# keyBoard_A.net
KiCad netlist of a schematic drawn in EAGLE
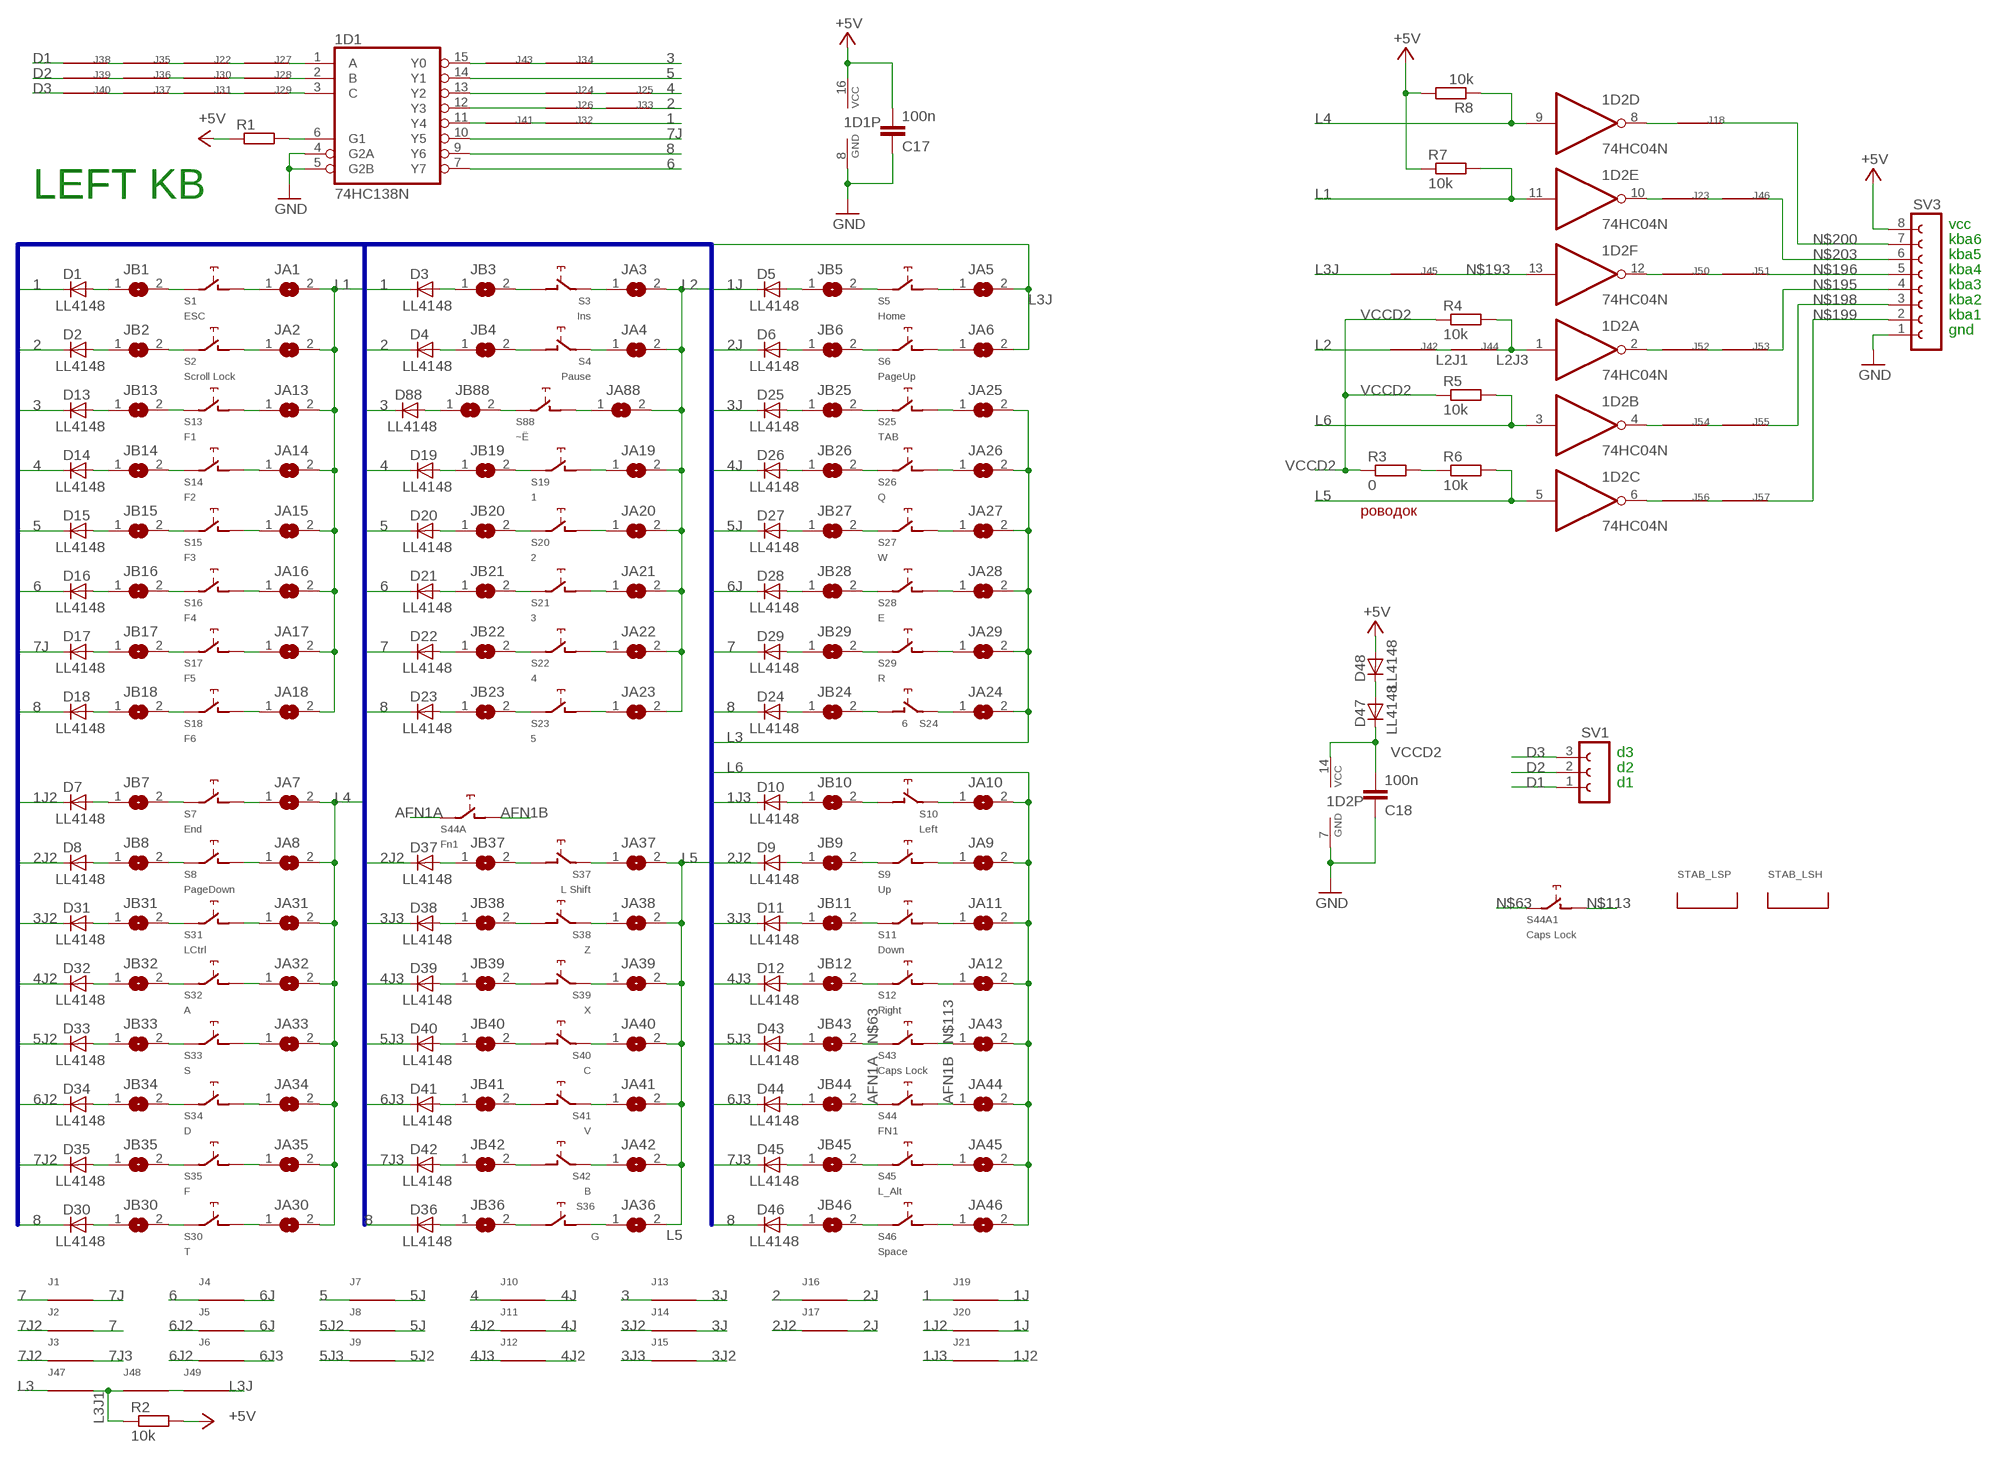
[diagram p0: schematic, sheet 1]

(export (version "E")
  (design (tool "Eeschema 10.0.6"))
  (components
    (comp (ref "1D1")
      (value "74HC138N")
      (footprint "eagle-import:DIL16")
      (libsource (lib "eagle-import") (part "74138NHC"))
    )
    (comp (ref "1D2")
      (value "74HC04N")
      (footprint "eagle-import:DIL14")
      (libsource (lib "eagle-import") (part "7404NACT"))
    )
    (comp (ref "C17")
      (value "100n")
      (footprint "eagle-import:C0805")
      (libsource (lib "eagle-import") (part "C-EUC0805"))
    )
    (comp (ref "C18")
      (value "100n")
      (footprint "eagle-import:C0805")
      (libsource (lib "eagle-import") (part "C-EUC0805"))
    )
    (comp (ref "D1")
      (value "LL4148")
      (footprint "eagle-import:SOD80C")
      (libsource (lib "eagle-import") (part "LL4148"))
    )
    (comp (ref "D2")
      (value "LL4148")
      (footprint "eagle-import:SOD80C")
      (libsource (lib "eagle-import") (part "LL4148"))
    )
    (comp (ref "D3")
      (value "LL4148")
      (footprint "eagle-import:SOD80C")
      (libsource (lib "eagle-import") (part "LL4148"))
    )
    (comp (ref "D4")
      (value "LL4148")
      (footprint "eagle-import:SOD80C")
      (libsource (lib "eagle-import") (part "LL4148"))
    )
    (comp (ref "D5")
      (value "LL4148")
      (footprint "eagle-import:SOD80C")
      (libsource (lib "eagle-import") (part "LL4148"))
    )
    (comp (ref "D6")
      (value "LL4148")
      (footprint "eagle-import:SOD80C")
      (libsource (lib "eagle-import") (part "LL4148"))
    )
    (comp (ref "D7")
      (value "LL4148")
      (footprint "eagle-import:SOD80C")
      (libsource (lib "eagle-import") (part "LL4148"))
    )
    (comp (ref "D8")
      (value "LL4148")
      (footprint "eagle-import:SOD80C")
      (libsource (lib "eagle-import") (part "LL4148"))
    )
    (comp (ref "D9")
      (value "LL4148")
      (footprint "eagle-import:SOD80C")
      (libsource (lib "eagle-import") (part "LL4148"))
    )
    (comp (ref "D10")
      (value "LL4148")
      (footprint "eagle-import:SOD80C")
      (libsource (lib "eagle-import") (part "LL4148"))
    )
    (comp (ref "D11")
      (value "LL4148")
      (footprint "eagle-import:SOD80C")
      (libsource (lib "eagle-import") (part "LL4148"))
    )
    (comp (ref "D12")
      (value "LL4148")
      (footprint "eagle-import:SOD80C")
      (libsource (lib "eagle-import") (part "LL4148"))
    )
    (comp (ref "D13")
      (value "LL4148")
      (footprint "eagle-import:SOD80C")
      (libsource (lib "eagle-import") (part "LL4148"))
    )
    (comp (ref "D14")
      (value "LL4148")
      (footprint "eagle-import:SOD80C")
      (libsource (lib "eagle-import") (part "LL4148"))
    )
    (comp (ref "D15")
      (value "LL4148")
      (footprint "eagle-import:SOD80C")
      (libsource (lib "eagle-import") (part "LL4148"))
    )
    (comp (ref "D16")
      (value "LL4148")
      (footprint "eagle-import:SOD80C")
      (libsource (lib "eagle-import") (part "LL4148"))
    )
    (comp (ref "D17")
      (value "LL4148")
      (footprint "eagle-import:SOD80C")
      (libsource (lib "eagle-import") (part "LL4148"))
    )
    (comp (ref "D18")
      (value "LL4148")
      (footprint "eagle-import:SOD80C")
      (libsource (lib "eagle-import") (part "LL4148"))
    )
    (comp (ref "D19")
      (value "LL4148")
      (footprint "eagle-import:SOD80C")
      (libsource (lib "eagle-import") (part "LL4148"))
    )
    (comp (ref "D20")
      (value "LL4148")
      (footprint "eagle-import:SOD80C")
      (libsource (lib "eagle-import") (part "LL4148"))
    )
    (comp (ref "D21")
      (value "LL4148")
      (footprint "eagle-import:SOD80C")
      (libsource (lib "eagle-import") (part "LL4148"))
    )
    (comp (ref "D22")
      (value "LL4148")
      (footprint "eagle-import:SOD80C")
      (libsource (lib "eagle-import") (part "LL4148"))
    )
    (comp (ref "D23")
      (value "LL4148")
      (footprint "eagle-import:SOD80C")
      (libsource (lib "eagle-import") (part "LL4148"))
    )
    (comp (ref "D24")
      (value "LL4148")
      (footprint "eagle-import:SOD80C")
      (libsource (lib "eagle-import") (part "LL4148"))
    )
    (comp (ref "D25")
      (value "LL4148")
      (footprint "eagle-import:SOD80C")
      (libsource (lib "eagle-import") (part "LL4148"))
    )
    (comp (ref "D26")
      (value "LL4148")
      (footprint "eagle-import:SOD80C")
      (libsource (lib "eagle-import") (part "LL4148"))
    )
    (comp (ref "D27")
      (value "LL4148")
      (footprint "eagle-import:SOD80C")
      (libsource (lib "eagle-import") (part "LL4148"))
    )
    (comp (ref "D28")
      (value "LL4148")
      (footprint "eagle-import:SOD80C")
      (libsource (lib "eagle-import") (part "LL4148"))
    )
    (comp (ref "D29")
      (value "LL4148")
      (footprint "eagle-import:SOD80C")
      (libsource (lib "eagle-import") (part "LL4148"))
    )
    (comp (ref "D30")
      (value "LL4148")
      (footprint "eagle-import:SOD80C")
      (libsource (lib "eagle-import") (part "LL4148"))
    )
    (comp (ref "D31")
      (value "LL4148")
      (footprint "eagle-import:SOD80C")
      (libsource (lib "eagle-import") (part "LL4148"))
    )
    (comp (ref "D32")
      (value "LL4148")
      (footprint "eagle-import:SOD80C")
      (libsource (lib "eagle-import") (part "LL4148"))
    )
    (comp (ref "D33")
      (value "LL4148")
      (footprint "eagle-import:SOD80C")
      (libsource (lib "eagle-import") (part "LL4148"))
    )
    (comp (ref "D34")
      (value "LL4148")
      (footprint "eagle-import:SOD80C")
      (libsource (lib "eagle-import") (part "LL4148"))
    )
    (comp (ref "D35")
      (value "LL4148")
      (footprint "eagle-import:SOD80C")
      (libsource (lib "eagle-import") (part "LL4148"))
    )
    (comp (ref "D36")
      (value "LL4148")
      (footprint "eagle-import:SOD80C")
      (libsource (lib "eagle-import") (part "LL4148"))
    )
    (comp (ref "D37")
      (value "LL4148")
      (footprint "eagle-import:SOD80C")
      (libsource (lib "eagle-import") (part "LL4148"))
    )
    (comp (ref "D38")
      (value "LL4148")
      (footprint "eagle-import:SOD80C")
      (libsource (lib "eagle-import") (part "LL4148"))
    )
    (comp (ref "D39")
      (value "LL4148")
      (footprint "eagle-import:SOD80C")
      (libsource (lib "eagle-import") (part "LL4148"))
    )
    (comp (ref "D40")
      (value "LL4148")
      (footprint "eagle-import:SOD80C")
      (libsource (lib "eagle-import") (part "LL4148"))
    )
    (comp (ref "D41")
      (value "LL4148")
      (footprint "eagle-import:SOD80C")
      (libsource (lib "eagle-import") (part "LL4148"))
    )
    (comp (ref "D42")
      (value "LL4148")
      (footprint "eagle-import:SOD80C")
      (libsource (lib "eagle-import") (part "LL4148"))
    )
    (comp (ref "D43")
      (value "LL4148")
      (footprint "eagle-import:SOD80C")
      (libsource (lib "eagle-import") (part "LL4148"))
    )
    (comp (ref "D44")
      (value "LL4148")
      (footprint "eagle-import:SOD80C")
      (libsource (lib "eagle-import") (part "LL4148"))
    )
    (comp (ref "D45")
      (value "LL4148")
      (footprint "eagle-import:SOD80C")
      (libsource (lib "eagle-import") (part "LL4148"))
    )
    (comp (ref "D46")
      (value "LL4148")
      (footprint "eagle-import:SOD80C")
      (libsource (lib "eagle-import") (part "LL4148"))
    )
    (comp (ref "D47")
      (value "LL4148")
      (footprint "eagle-import:SOD80C")
      (libsource (lib "eagle-import") (part "LL4148"))
    )
    (comp (ref "D48")
      (value "LL4148")
      (footprint "eagle-import:SOD80C")
      (libsource (lib "eagle-import") (part "LL4148"))
    )
    (comp (ref "D88")
      (value "LL4148")
      (footprint "eagle-import:SOD80C")
      (libsource (lib "eagle-import") (part "LL4148"))
    )
    (comp (ref "J1")
      (value "J")
      (footprint "eagle-import:R1206W")
      (libsource (lib "eagle-import") (part "J"))
    )
    (comp (ref "J2")
      (value "J")
      (footprint "eagle-import:R1206W")
      (libsource (lib "eagle-import") (part "J"))
    )
    (comp (ref "J3")
      (value "J")
      (footprint "eagle-import:R1206W")
      (libsource (lib "eagle-import") (part "J"))
    )
    (comp (ref "J4")
      (value "J")
      (footprint "eagle-import:R1206W")
      (libsource (lib "eagle-import") (part "J"))
    )
    (comp (ref "J5")
      (value "J")
      (footprint "eagle-import:R1206W")
      (libsource (lib "eagle-import") (part "J"))
    )
    (comp (ref "J6")
      (value "J")
      (footprint "eagle-import:R1206W")
      (libsource (lib "eagle-import") (part "J"))
    )
    (comp (ref "J7")
      (value "J")
      (footprint "eagle-import:R1206W")
      (libsource (lib "eagle-import") (part "J"))
    )
    (comp (ref "J8")
      (value "J")
      (footprint "eagle-import:R1206W")
      (libsource (lib "eagle-import") (part "J"))
    )
    (comp (ref "J9")
      (value "J")
      (footprint "eagle-import:R1206W")
      (libsource (lib "eagle-import") (part "J"))
    )
    (comp (ref "J10")
      (value "J")
      (footprint "eagle-import:R1206W")
      (libsource (lib "eagle-import") (part "J"))
    )
    (comp (ref "J11")
      (value "J")
      (footprint "eagle-import:R1206W")
      (libsource (lib "eagle-import") (part "J"))
    )
    (comp (ref "J12")
      (value "J")
      (footprint "eagle-import:R1206W")
      (libsource (lib "eagle-import") (part "J"))
    )
    (comp (ref "J13")
      (value "J")
      (footprint "eagle-import:R1206W")
      (libsource (lib "eagle-import") (part "J"))
    )
    (comp (ref "J14")
      (value "J")
      (footprint "eagle-import:R1206W")
      (libsource (lib "eagle-import") (part "J"))
    )
    (comp (ref "J15")
      (value "J")
      (footprint "eagle-import:R1206W")
      (libsource (lib "eagle-import") (part "J"))
    )
    (comp (ref "J16")
      (value "J")
      (footprint "eagle-import:R1206W")
      (libsource (lib "eagle-import") (part "J"))
    )
    (comp (ref "J17")
      (value "J")
      (footprint "eagle-import:R1206W")
      (libsource (lib "eagle-import") (part "J"))
    )
    (comp (ref "J18")
      (value "J")
      (footprint "eagle-import:R1206W")
      (libsource (lib "eagle-import") (part "J"))
    )
    (comp (ref "J19")
      (value "J")
      (footprint "eagle-import:R1206W")
      (libsource (lib "eagle-import") (part "J"))
    )
    (comp (ref "J20")
      (value "J")
      (footprint "eagle-import:R1206W")
      (libsource (lib "eagle-import") (part "J"))
    )
    (comp (ref "J21")
      (value "J")
      (footprint "eagle-import:R1206W")
      (libsource (lib "eagle-import") (part "J"))
    )
    (comp (ref "J22")
      (value "J")
      (footprint "eagle-import:R1206W")
      (libsource (lib "eagle-import") (part "J"))
    )
    (comp (ref "J23")
      (value "J")
      (footprint "eagle-import:R1206W")
      (libsource (lib "eagle-import") (part "J"))
    )
    (comp (ref "J24")
      (value "J")
      (footprint "eagle-import:R1206W")
      (libsource (lib "eagle-import") (part "J"))
    )
    (comp (ref "J25")
      (value "J")
      (footprint "eagle-import:R1206W")
      (libsource (lib "eagle-import") (part "J"))
    )
    (comp (ref "J26")
      (value "J")
      (footprint "eagle-import:R1206W")
      (libsource (lib "eagle-import") (part "J"))
    )
    (comp (ref "J27")
      (value "J")
      (footprint "eagle-import:R1206W")
      (libsource (lib "eagle-import") (part "J"))
    )
    (comp (ref "J28")
      (value "J")
      (footprint "eagle-import:R1206W")
      (libsource (lib "eagle-import") (part "J"))
    )
    (comp (ref "J29")
      (value "J")
      (footprint "eagle-import:R1206W")
      (libsource (lib "eagle-import") (part "J"))
    )
    (comp (ref "J30")
      (value "J")
      (footprint "eagle-import:R1206W")
      (libsource (lib "eagle-import") (part "J"))
    )
    (comp (ref "J31")
      (value "J")
      (footprint "eagle-import:R1206W")
      (libsource (lib "eagle-import") (part "J"))
    )
    (comp (ref "J32")
      (value "J")
      (footprint "eagle-import:R1206W")
      (libsource (lib "eagle-import") (part "J"))
    )
    (comp (ref "J33")
      (value "J")
      (footprint "eagle-import:R1206W")
      (libsource (lib "eagle-import") (part "J"))
    )
    (comp (ref "J34")
      (value "J")
      (footprint "eagle-import:R1206W")
      (libsource (lib "eagle-import") (part "J"))
    )
    (comp (ref "J35")
      (value "J")
      (footprint "eagle-import:R1206W")
      (libsource (lib "eagle-import") (part "J"))
    )
    (comp (ref "J36")
      (value "J")
      (footprint "eagle-import:R1206W")
      (libsource (lib "eagle-import") (part "J"))
    )
    (comp (ref "J37")
      (value "J")
      (footprint "eagle-import:R1206W")
      (libsource (lib "eagle-import") (part "J"))
    )
    (comp (ref "J38")
      (value "J")
      (footprint "eagle-import:R1206W")
      (libsource (lib "eagle-import") (part "J"))
    )
    (comp (ref "J39")
      (value "J")
      (footprint "eagle-import:R1206W")
      (libsource (lib "eagle-import") (part "J"))
    )
    (comp (ref "J40")
      (value "J")
      (footprint "eagle-import:R1206W")
      (libsource (lib "eagle-import") (part "J"))
    )
    (comp (ref "J41")
      (value "J")
      (footprint "eagle-import:R1206W")
      (libsource (lib "eagle-import") (part "J"))
    )
    (comp (ref "J42")
      (value "J")
      (footprint "eagle-import:R1206W")
      (libsource (lib "eagle-import") (part "J"))
    )
    (comp (ref "J43")
      (value "J")
      (footprint "eagle-import:R1206W")
      (libsource (lib "eagle-import") (part "J"))
    )
    (comp (ref "J44")
      (value "J")
      (footprint "eagle-import:R1206W")
      (libsource (lib "eagle-import") (part "J"))
    )
    (comp (ref "J45")
      (value "J")
      (footprint "eagle-import:R1206W")
      (libsource (lib "eagle-import") (part "J"))
    )
    (comp (ref "J46")
      (value "J")
      (footprint "eagle-import:R1206W")
      (libsource (lib "eagle-import") (part "J"))
    )
    (comp (ref "J47")
      (value "J")
      (footprint "eagle-import:R1206W")
      (libsource (lib "eagle-import") (part "J"))
    )
    (comp (ref "J48")
      (value "J")
      (footprint "eagle-import:R1206W")
      (libsource (lib "eagle-import") (part "J"))
    )
    (comp (ref "J49")
      (value "J")
      (footprint "eagle-import:R1206W")
      (libsource (lib "eagle-import") (part "J"))
    )
    (comp (ref "J50")
      (value "J")
      (footprint "eagle-import:R1206W")
      (libsource (lib "eagle-import") (part "J"))
    )
    (comp (ref "J51")
      (value "J")
      (footprint "eagle-import:R1206W")
      (libsource (lib "eagle-import") (part "J"))
    )
    (comp (ref "J52")
      (value "J")
      (footprint "eagle-import:R1206W")
      (libsource (lib "eagle-import") (part "J"))
    )
    (comp (ref "J53")
      (value "J")
      (footprint "eagle-import:R1206W")
      (libsource (lib "eagle-import") (part "J"))
    )
    (comp (ref "J54")
      (value "J")
      (footprint "eagle-import:R1206W")
      (libsource (lib "eagle-import") (part "J"))
    )
    (comp (ref "J55")
      (value "J")
      (footprint "eagle-import:R1206W")
      (libsource (lib "eagle-import") (part "J"))
    )
    (comp (ref "J56")
      (value "J")
      (footprint "eagle-import:R1206W")
      (libsource (lib "eagle-import") (part "J"))
    )
    (comp (ref "J57")
      (value "J")
      (footprint "eagle-import:R1206W")
      (libsource (lib "eagle-import") (part "J"))
    )
    (comp (ref "JA1")
      (value "SJ")
      (footprint "eagle-import:SJ")
      (libsource (lib "eagle-import") (part "detali_main_SJ"))
    )
    (comp (ref "JA2")
      (value "SJ")
      (footprint "eagle-import:SJ")
      (libsource (lib "eagle-import") (part "detali_main_SJ"))
    )
    (comp (ref "JA3")
      (value "SJ")
      (footprint "eagle-import:SJ")
      (libsource (lib "eagle-import") (part "detali_main_SJ"))
    )
    (comp (ref "JA4")
      (value "SJ")
      (footprint "eagle-import:SJ")
      (libsource (lib "eagle-import") (part "detali_main_SJ"))
    )
    (comp (ref "JA5")
      (value "SJ")
      (footprint "eagle-import:SJ")
      (libsource (lib "eagle-import") (part "detali_main_SJ"))
    )
    (comp (ref "JA6")
      (value "SJ")
      (footprint "eagle-import:SJ")
      (libsource (lib "eagle-import") (part "detali_main_SJ"))
    )
    (comp (ref "JA7")
      (value "SJ")
      (footprint "eagle-import:SJ")
      (libsource (lib "eagle-import") (part "detali_main_SJ"))
    )
    (comp (ref "JA8")
      (value "SJ")
      (footprint "eagle-import:SJ")
      (libsource (lib "eagle-import") (part "detali_main_SJ"))
    )
    (comp (ref "JA9")
      (value "SJ")
      (footprint "eagle-import:SJ")
      (libsource (lib "eagle-import") (part "detali_main_SJ"))
    )
    (comp (ref "JA10")
      (value "SJ")
      (footprint "eagle-import:SJ")
      (libsource (lib "eagle-import") (part "detali_main_SJ"))
    )
    (comp (ref "JA11")
      (value "SJ")
      (footprint "eagle-import:SJ")
      (libsource (lib "eagle-import") (part "detali_main_SJ"))
    )
    (comp (ref "JA12")
      (value "SJ")
      (footprint "eagle-import:SJ")
      (libsource (lib "eagle-import") (part "detali_main_SJ"))
    )
    (comp (ref "JA13")
      (value "SJ")
      (footprint "eagle-import:SJ")
      (libsource (lib "eagle-import") (part "SJ"))
    )
    (comp (ref "JA14")
      (value "SJ")
      (footprint "eagle-import:SJ")
      (libsource (lib "eagle-import") (part "SJ"))
    )
    (comp (ref "JA15")
      (value "SJ")
      (footprint "eagle-import:SJ")
      (libsource (lib "eagle-import") (part "SJ"))
    )
    (comp (ref "JA16")
      (value "SJ")
      (footprint "eagle-import:SJ")
      (libsource (lib "eagle-import") (part "SJ"))
    )
    (comp (ref "JA17")
      (value "SJ")
      (footprint "eagle-import:SJ")
      (libsource (lib "eagle-import") (part "SJ"))
    )
    (comp (ref "JA18")
      (value "SJ")
      (footprint "eagle-import:SJ")
      (libsource (lib "eagle-import") (part "SJ"))
    )
    (comp (ref "JA19")
      (value "SJ")
      (footprint "eagle-import:SJ")
      (libsource (lib "eagle-import") (part "SJ"))
    )
    (comp (ref "JA20")
      (value "SJ")
      (footprint "eagle-import:SJ")
      (libsource (lib "eagle-import") (part "SJ"))
    )
    (comp (ref "JA21")
      (value "SJ")
      (footprint "eagle-import:SJ")
      (libsource (lib "eagle-import") (part "SJ"))
    )
    (comp (ref "JA22")
      (value "SJ")
      (footprint "eagle-import:SJ")
      (libsource (lib "eagle-import") (part "SJ"))
    )
    (comp (ref "JA23")
      (value "SJ")
      (footprint "eagle-import:SJ")
      (libsource (lib "eagle-import") (part "SJ"))
    )
    (comp (ref "JA24")
      (value "SJ")
      (footprint "eagle-import:SJ")
      (libsource (lib "eagle-import") (part "SJ"))
    )
    (comp (ref "JA25")
      (value "SJ")
      (footprint "eagle-import:SJ")
      (libsource (lib "eagle-import") (part "SJ"))
    )
    (comp (ref "JA26")
      (value "SJ")
      (footprint "eagle-import:SJ")
      (libsource (lib "eagle-import") (part "SJ"))
    )
    (comp (ref "JA27")
      (value "SJ")
      (footprint "eagle-import:SJ")
      (libsource (lib "eagle-import") (part "SJ"))
    )
    (comp (ref "JA28")
      (value "SJ")
      (footprint "eagle-import:SJ")
      (libsource (lib "eagle-import") (part "SJ"))
    )
    (comp (ref "JA29")
      (value "SJ")
      (footprint "eagle-import:SJ")
      (libsource (lib "eagle-import") (part "SJ"))
    )
    (comp (ref "JA30")
      (value "SJ")
      (footprint "eagle-import:SJ")
      (libsource (lib "eagle-import") (part "SJ"))
    )
    (comp (ref "JA31")
      (value "SJ")
      (footprint "eagle-import:SJ")
      (libsource (lib "eagle-import") (part "SJ"))
    )
    (comp (ref "JA32")
      (value "SJ")
      (footprint "eagle-import:SJ")
      (libsource (lib "eagle-import") (part "SJ"))
    )
    (comp (ref "JA33")
      (value "SJ")
      (footprint "eagle-import:SJ")
      (libsource (lib "eagle-import") (part "SJ"))
    )
    (comp (ref "JA34")
      (value "SJ")
      (footprint "eagle-import:SJ")
      (libsource (lib "eagle-import") (part "SJ"))
    )
    (comp (ref "JA35")
      (value "SJ")
      (footprint "eagle-import:SJ")
      (libsource (lib "eagle-import") (part "SJ"))
    )
    (comp (ref "JA36")
      (value "SJ")
      (footprint "eagle-import:SJ")
      (libsource (lib "eagle-import") (part "SJ"))
    )
    (comp (ref "JA37")
      (value "SJ")
      (footprint "eagle-import:SJ")
      (libsource (lib "eagle-import") (part "SJ"))
    )
    (comp (ref "JA38")
      (value "SJ")
      (footprint "eagle-import:SJ")
      (libsource (lib "eagle-import") (part "SJ"))
    )
    (comp (ref "JA39")
      (value "SJ")
      (footprint "eagle-import:SJ")
      (libsource (lib "eagle-import") (part "SJ"))
    )
    (comp (ref "JA40")
      (value "SJ")
      (footprint "eagle-import:SJ")
      (libsource (lib "eagle-import") (part "SJ"))
    )
    (comp (ref "JA41")
      (value "SJ")
      (footprint "eagle-import:SJ")
      (libsource (lib "eagle-import") (part "SJ"))
    )
    (comp (ref "JA42")
      (value "SJ")
      (footprint "eagle-import:SJ")
      (libsource (lib "eagle-import") (part "SJ"))
    )
    (comp (ref "JA43")
      (value "SJ")
      (footprint "eagle-import:SJ")
      (libsource (lib "eagle-import") (part "detali_main_SJ"))
    )
    (comp (ref "JA44")
      (value "SJ")
      (footprint "eagle-import:SJ")
      (libsource (lib "eagle-import") (part "SJ"))
    )
    (comp (ref "JA45")
      (value "SJ")
      (footprint "eagle-import:SJ")
      (libsource (lib "eagle-import") (part "SJ"))
    )
    (comp (ref "JA46")
      (value "SJ")
      (footprint "eagle-import:SJ")
      (libsource (lib "eagle-import") (part "SJ"))
    )
    (comp (ref "JA88")
      (value "SJ")
      (footprint "eagle-import:SJ")
      (libsource (lib "eagle-import") (part "SJ"))
    )
    (comp (ref "JB1") (value "SJ") (footprint "eagle-import:SJ") (libsource (lib "eagle-import") (part "SJ")))
    (comp (ref "JB2")
      (value "SJ")
      (footprint "eagle-import:SJ@1")
      (libsource (lib "eagle-import") (part "jumper_SJ"))
    )
    (comp (ref "JB3") (value "SJ") (footprint "eagle-import:SJ") (libsource (lib "eagle-import") (part "SJ")))
    (comp (ref "JB4")
      (value "SJ")
      (footprint "eagle-import:SJ")
      (libsource (lib "eagle-import") (part "detali_main_SJ"))
    )
    (comp (ref "JB5")
      (value "SJ")
      (footprint "eagle-import:SJ@1")
      (libsource (lib "eagle-import") (part "jumper_SJ"))
    )
    (comp (ref "JB6")
      (value "SJ")
      (footprint "eagle-import:SJ")
      (libsource (lib "eagle-import") (part "detali_main_SJ"))
    )
    (comp (ref "JB7")
      (value "SJ")
      (footprint "eagle-import:SJ")
      (libsource (lib "eagle-import") (part "detali_main_SJ"))
    )
    (comp (ref "JB8")
      (value "SJ")
      (footprint "eagle-import:SJ")
      (libsource (lib "eagle-import") (part "detali_main_SJ"))
    )
    (comp (ref "JB9")
      (value "SJ")
      (footprint "eagle-import:SJ")
      (libsource (lib "eagle-import") (part "detali_main_SJ"))
    )
    (comp (ref "JB10")
      (value "SJ")
      (footprint "eagle-import:SJ")
      (libsource (lib "eagle-import") (part "detali_main_SJ"))
    )
    (comp (ref "JB11")
      (value "SJ")
      (footprint "eagle-import:SJ")
      (libsource (lib "eagle-import") (part "detali_main_SJ"))
    )
    (comp (ref "JB12")
      (value "SJ")
      (footprint "eagle-import:SJ")
      (libsource (lib "eagle-import") (part "detali_main_SJ"))
    )
    (comp (ref "JB13")
      (value "SJ")
      (footprint "eagle-import:SJ")
      (libsource (lib "eagle-import") (part "detali_main_SJ"))
    )
    (comp (ref "JB14")
      (value "SJ")
      (footprint "eagle-import:SJ@1")
      (libsource (lib "eagle-import") (part "jumper_SJ"))
    )
    (comp (ref "JB15")
      (value "SJ")
      (footprint "eagle-import:SJ@1")
      (libsource (lib "eagle-import") (part "jumper_SJ"))
    )
    (comp (ref "JB16")
      (value "SJ")
      (footprint "eagle-import:SJ")
      (libsource (lib "eagle-import") (part "detali_main_SJ"))
    )
    (comp (ref "JB17")
      (value "SJ")
      (footprint "eagle-import:SJ")
      (libsource (lib "eagle-import") (part "detali_main_SJ"))
    )
    (comp (ref "JB18")
      (value "SJ")
      (footprint "eagle-import:SJ")
      (libsource (lib "eagle-import") (part "SJ"))
    )
    (comp (ref "JB19")
      (value "SJ")
      (footprint "eagle-import:SJ")
      (libsource (lib "eagle-import") (part "SJ"))
    )
    (comp (ref "JB20")
      (value "SJ")
      (footprint "eagle-import:SJ")
      (libsource (lib "eagle-import") (part "SJ"))
    )
    (comp (ref "JB21")
      (value "SJ")
      (footprint "eagle-import:SJ")
      (libsource (lib "eagle-import") (part "SJ"))
    )
    (comp (ref "JB22")
      (value "SJ")
      (footprint "eagle-import:SJ")
      (libsource (lib "eagle-import") (part "SJ"))
    )
    (comp (ref "JB23")
      (value "SJ")
      (footprint "eagle-import:SJ")
      (libsource (lib "eagle-import") (part "SJ"))
    )
    (comp (ref "JB24")
      (value "SJ")
      (footprint "eagle-import:SJ")
      (libsource (lib "eagle-import") (part "SJ"))
    )
    (comp (ref "JB25")
      (value "SJ")
      (footprint "eagle-import:SJ")
      (libsource (lib "eagle-import") (part "SJ"))
    )
    (comp (ref "JB26")
      (value "SJ")
      (footprint "eagle-import:SJ")
      (libsource (lib "eagle-import") (part "SJ"))
    )
    (comp (ref "JB27")
      (value "SJ")
      (footprint "eagle-import:SJ")
      (libsource (lib "eagle-import") (part "SJ"))
    )
    (comp (ref "JB28")
      (value "SJ")
      (footprint "eagle-import:SJ")
      (libsource (lib "eagle-import") (part "SJ"))
    )
    (comp (ref "JB29")
      (value "SJ")
      (footprint "eagle-import:SJ")
      (libsource (lib "eagle-import") (part "SJ"))
    )
    (comp (ref "JB30")
      (value "SJ")
      (footprint "eagle-import:SJ")
      (libsource (lib "eagle-import") (part "SJ"))
    )
    (comp (ref "JB31")
      (value "SJ")
      (footprint "eagle-import:SJ")
      (libsource (lib "eagle-import") (part "SJ"))
    )
    (comp (ref "JB32")
      (value "SJ")
      (footprint "eagle-import:SJ")
      (libsource (lib "eagle-import") (part "SJ"))
    )
    (comp (ref "JB33")
      (value "SJ")
      (footprint "eagle-import:SJ")
      (libsource (lib "eagle-import") (part "SJ"))
    )
    (comp (ref "JB34")
      (value "SJ")
      (footprint "eagle-import:SJ")
      (libsource (lib "eagle-import") (part "SJ"))
    )
    (comp (ref "JB35")
      (value "SJ")
      (footprint "eagle-import:SJ")
      (libsource (lib "eagle-import") (part "SJ"))
    )
    (comp (ref "JB36")
      (value "SJ")
      (footprint "eagle-import:SJ")
      (libsource (lib "eagle-import") (part "SJ"))
    )
    (comp (ref "JB37")
      (value "SJ")
      (footprint "eagle-import:SJ")
      (libsource (lib "eagle-import") (part "SJ"))
    )
    (comp (ref "JB38")
      (value "SJ")
      (footprint "eagle-import:SJ")
      (libsource (lib "eagle-import") (part "SJ"))
    )
    (comp (ref "JB39")
      (value "SJ")
      (footprint "eagle-import:SJ")
      (libsource (lib "eagle-import") (part "SJ"))
    )
    (comp (ref "JB40")
      (value "SJ")
      (footprint "eagle-import:SJ")
      (libsource (lib "eagle-import") (part "SJ"))
    )
    (comp (ref "JB41")
      (value "SJ")
      (footprint "eagle-import:SJ")
      (libsource (lib "eagle-import") (part "SJ"))
    )
    (comp (ref "JB42")
      (value "SJ")
      (footprint "eagle-import:SJ")
      (libsource (lib "eagle-import") (part "SJ"))
    )
    (comp (ref "JB43")
      (value "SJ")
      (footprint "eagle-import:SJ")
      (libsource (lib "eagle-import") (part "SJ"))
    )
    (comp (ref "JB44")
      (value "SJ")
      (footprint "eagle-import:SJ")
      (libsource (lib "eagle-import") (part "SJ"))
    )
    (comp (ref "JB45")
      (value "SJ")
      (footprint "eagle-import:SJ")
      (libsource (lib "eagle-import") (part "SJ"))
    )
    (comp (ref "JB46")
      (value "SJ")
      (footprint "eagle-import:SJ")
      (libsource (lib "eagle-import") (part "SJ"))
    )
    (comp (ref "JB88")
      (value "SJ")
      (footprint "eagle-import:SJ")
      (libsource (lib "eagle-import") (part "SJ"))
    )
    (comp (ref "R1")
      (value "R-EU_R1206W")
      (footprint "eagle-import:R1206W")
      (libsource (lib "eagle-import") (part "R-EU_R1206W"))
    )
    (comp (ref "R2")
      (value "10k")
      (footprint "eagle-import:R1206W")
      (libsource (lib "eagle-import") (part "R-EU_R1206W"))
    )
    (comp (ref "R3")
      (value "0")
      (footprint "eagle-import:R1206W")
      (libsource (lib "eagle-import") (part "R-EU_R1206W"))
    )
    (comp (ref "R4")
      (value "10k")
      (footprint "eagle-import:R0805")
      (libsource (lib "eagle-import") (part "R-EU_R0805"))
    )
    (comp (ref "R5")
      (value "10k")
      (footprint "eagle-import:R1206W")
      (libsource (lib "eagle-import") (part "R-EU_R1206W"))
    )
    (comp (ref "R6")
      (value "10k")
      (footprint "eagle-import:R1206W")
      (libsource (lib "eagle-import") (part "R-EU_R1206W"))
    )
    (comp (ref "R7")
      (value "10k")
      (footprint "eagle-import:R1206W")
      (libsource (lib "eagle-import") (part "R-EU_R1206W"))
    )
    (comp (ref "R8")
      (value "10k")
      (footprint "eagle-import:R0805")
      (libsource (lib "eagle-import") (part "R-EU_R0805"))
    )
    (comp (ref "S1")
      (value "ESC")
      (footprint "eagle-import:CHERRY-MX-4P")
      (libsource (lib "eagle-import") (part "CHERRY-MX-4P"))
    )
    (comp (ref "S2")
      (value "Scroll Lock")
      (footprint "eagle-import:CHERRY-MX-4P")
      (libsource (lib "eagle-import") (part "CHERRY-MX-4P"))
    )
    (comp (ref "S3")
      (value "Ins")
      (footprint "eagle-import:CHERRY-MX-4P")
      (libsource (lib "eagle-import") (part "CHERRY-MX-4P"))
    )
    (comp (ref "S4")
      (value "Pause")
      (footprint "eagle-import:CHERRY-MX-4P")
      (libsource (lib "eagle-import") (part "CHERRY-MX-4P"))
    )
    (comp (ref "S5")
      (value "Home")
      (footprint "eagle-import:CHERRY-MX-4P")
      (libsource (lib "eagle-import") (part "CHERRY-MX-4P"))
    )
    (comp (ref "S6")
      (value "PageUp")
      (footprint "eagle-import:CHERRY-MX-4P")
      (libsource (lib "eagle-import") (part "CHERRY-MX-4P"))
    )
    (comp (ref "S7")
      (value "End")
      (footprint "eagle-import:CHERRY-MX-4P")
      (libsource (lib "eagle-import") (part "CHERRY-MX-4P"))
    )
    (comp (ref "S8")
      (value "PageDown")
      (footprint "eagle-import:CHERRY-MX-4P")
      (libsource (lib "eagle-import") (part "CHERRY-MX-4P"))
    )
    (comp (ref "S9")
      (value "Up")
      (footprint "eagle-import:CHERRY-MX-4P")
      (libsource (lib "eagle-import") (part "CHERRY-MX-4P"))
    )
    (comp (ref "S10")
      (value "Left")
      (footprint "eagle-import:CHERRY-MX-4P")
      (libsource (lib "eagle-import") (part "CHERRY-MX-4P"))
    )
    (comp (ref "S11")
      (value "Down")
      (footprint "eagle-import:CHERRY-MX-4P")
      (libsource (lib "eagle-import") (part "CHERRY-MX-4P"))
    )
    (comp (ref "S12")
      (value "Right")
      (footprint "eagle-import:CHERRY-MX-4P")
      (libsource (lib "eagle-import") (part "CHERRY-MX-4P"))
    )
    (comp (ref "S13")
      (value "F1")
      (footprint "eagle-import:CHERRY-MX-4P")
      (libsource (lib "eagle-import") (part "CHERRY-MX-4P"))
    )
    (comp (ref "S14")
      (value "F2")
      (footprint "eagle-import:CHERRY-MX-4P")
      (libsource (lib "eagle-import") (part "CHERRY-MX-4P"))
    )
    (comp (ref "S15")
      (value "F3")
      (footprint "eagle-import:CHERRY-MX-4P")
      (libsource (lib "eagle-import") (part "CHERRY-MX-4P"))
    )
    (comp (ref "S16")
      (value "F4")
      (footprint "eagle-import:CHERRY-MX-4P")
      (libsource (lib "eagle-import") (part "CHERRY-MX-4P"))
    )
    (comp (ref "S17")
      (value "F5")
      (footprint "eagle-import:CHERRY-MX-4P")
      (libsource (lib "eagle-import") (part "CHERRY-MX-4P"))
    )
    (comp (ref "S18")
      (value "F6")
      (footprint "eagle-import:CHERRY-MX-4P")
      (libsource (lib "eagle-import") (part "CHERRY-MX-4P"))
    )
    (comp (ref "S19")
      (value "1")
      (footprint "eagle-import:CHERRY-MX-4P")
      (libsource (lib "eagle-import") (part "CHERRY-MX-4P"))
    )
    (comp (ref "S20")
      (value "2")
      (footprint "eagle-import:CHERRY-MX-4P")
      (libsource (lib "eagle-import") (part "CHERRY-MX-4P"))
    )
    (comp (ref "S21")
      (value "3")
      (footprint "eagle-import:CHERRY-MX-4P")
      (libsource (lib "eagle-import") (part "CHERRY-MX-4P"))
    )
    (comp (ref "S22")
      (value "4")
      (footprint "eagle-import:CHERRY-MX-4P")
      (libsource (lib "eagle-import") (part "CHERRY-MX-4P"))
    )
    (comp (ref "S23")
      (value "5")
      (footprint "eagle-import:CHERRY-MX-4P")
      (libsource (lib "eagle-import") (part "CHERRY-MX-4P"))
    )
    (comp (ref "S24")
      (value "6")
      (footprint "eagle-import:CHERRY-MX-4P")
      (libsource (lib "eagle-import") (part "CHERRY-MX-4P"))
    )
    (comp (ref "S25")
      (value "TAB")
      (footprint "eagle-import:CHERRY-MX-4P")
      (libsource (lib "eagle-import") (part "CHERRY-MX-4P"))
    )
    (comp (ref "S26")
      (value "Q")
      (footprint "eagle-import:CHERRY-MX-4P")
      (libsource (lib "eagle-import") (part "CHERRY-MX-4P"))
    )
    (comp (ref "S27")
      (value "W")
      (footprint "eagle-import:CHERRY-MX-4P")
      (libsource (lib "eagle-import") (part "CHERRY-MX-4P"))
    )
    (comp (ref "S28")
      (value "E")
      (footprint "eagle-import:CHERRY-MX-4P")
      (libsource (lib "eagle-import") (part "CHERRY-MX-4P"))
    )
    (comp (ref "S29")
      (value "R")
      (footprint "eagle-import:CHERRY-MX-4P")
      (libsource (lib "eagle-import") (part "CHERRY-MX-4P"))
    )
    (comp (ref "S30")
      (value "T")
      (footprint "eagle-import:CHERRY-MX-4P")
      (libsource (lib "eagle-import") (part "CHERRY-MX-4P"))
    )
    (comp (ref "S31")
      (value "LCtrl")
      (footprint "eagle-import:CHERRY-MX-4P")
      (libsource (lib "eagle-import") (part "CHERRY-MX-4P"))
    )
    (comp (ref "S32")
      (value "A")
      (footprint "eagle-import:CHERRY-MX-4P")
      (libsource (lib "eagle-import") (part "CHERRY-MX-4P"))
    )
    (comp (ref "S33")
      (value "S")
      (footprint "eagle-import:CHERRY-MX-4P")
      (libsource (lib "eagle-import") (part "CHERRY-MX-4P"))
    )
    (comp (ref "S34")
      (value "D")
      (footprint "eagle-import:CHERRY-MX-4P")
      (libsource (lib "eagle-import") (part "CHERRY-MX-4P"))
    )
    (comp (ref "S35")
      (value "F")
      (footprint "eagle-import:CHERRY-MX-4P")
      (libsource (lib "eagle-import") (part "CHERRY-MX-4P"))
    )
    (comp (ref "S36")
      (value "G")
      (footprint "eagle-import:CHERRY-MX-4P")
      (libsource (lib "eagle-import") (part "CHERRY-MX-4P"))
    )
    (comp (ref "S37")
      (value "L Shift")
      (footprint "eagle-import:CHERRY-MX-4P")
      (libsource (lib "eagle-import") (part "CHERRY-MX-4P"))
    )
    (comp (ref "S38")
      (value "Z")
      (footprint "eagle-import:CHERRY-MX-4P")
      (libsource (lib "eagle-import") (part "CHERRY-MX-4P"))
    )
    (comp (ref "S39")
      (value "X")
      (footprint "eagle-import:CHERRY-MX-4P")
      (libsource (lib "eagle-import") (part "CHERRY-MX-4P"))
    )
    (comp (ref "S40")
      (value "C")
      (footprint "eagle-import:CHERRY-MX-4P")
      (libsource (lib "eagle-import") (part "CHERRY-MX-4P"))
    )
    (comp (ref "S41")
      (value "V")
      (footprint "eagle-import:CHERRY-MX-4P")
      (libsource (lib "eagle-import") (part "CHERRY-MX-4P"))
    )
    (comp (ref "S42")
      (value "B")
      (footprint "eagle-import:CHERRY-MX-4P")
      (libsource (lib "eagle-import") (part "CHERRY-MX-4P"))
    )
    (comp (ref "S43")
      (value "Caps Lock")
      (footprint "eagle-import:CHERRY-MX-4P")
      (libsource (lib "eagle-import") (part "CHERRY-MX-4P"))
    )
    (comp (ref "S44")
      (value "FN1")
      (footprint "eagle-import:CHERRY-MX-4P")
      (libsource (lib "eagle-import") (part "CHERRY-MX-4P"))
    )
    (comp (ref "S44A")
      (value "Fn1")
      (footprint "eagle-import:CHERRY-MX")
      (libsource (lib "eagle-import") (part "CHERRY-MX"))
    )
    (comp (ref "S44A1")
      (value "Caps Lock")
      (footprint "eagle-import:CHERRY-MX")
      (libsource (lib "eagle-import") (part "CHERRY-MX"))
    )
    (comp (ref "S45")
      (value "L_Alt")
      (footprint "eagle-import:CHERRY-MX-4P")
      (libsource (lib "eagle-import") (part "CHERRY-MX-4P"))
    )
    (comp (ref "S46")
      (value "Space")
      (footprint "eagle-import:CHERRY-MX-4P")
      (libsource (lib "eagle-import") (part "CHERRY-MX-4P"))
    )
    (comp (ref "S88")
      (value "~Ё")
      (footprint "eagle-import:CHERRY-MX-4P")
      (libsource (lib "eagle-import") (part "CHERRY-MX-4P"))
    )
    (comp (ref "STAB_LSH")
      (value "STAB")
      (footprint "eagle-import:ZEALIOS-PCB_2U")
      (libsource (lib "eagle-import") (part "STAB"))
    )
    (comp (ref "STAB_LSP")
      (value "STAB")
      (footprint "eagle-import:ZEALIOS-PCB_2U")
      (libsource (lib "eagle-import") (part "STAB"))
    )
    (comp (ref "SV1")
      (value "FE03-1")
      (footprint "eagle-import:FE03-1")
      (libsource (lib "eagle-import") (part "FE03-1"))
    )
    (comp (ref "SV3")
      (value "FE08-1")
      (footprint "eagle-import:FE08")
      (libsource (lib "eagle-import") (part "FE08-1"))
    )
  )
  (nets
    (net (code "1") (name "+5V") (class "Default")
      (node (ref "1D1") (pin "16") (pinfunction "VCC_16") (pintype "power_in"))
      (node (ref "C17") (pin "2") (pinfunction "2_2") (pintype "passive"))
      (node (ref "D48") (pin "A") (pinfunction "A_A") (pintype "passive"))
      (node (ref "R1") (pin "1") (pinfunction "1_1") (pintype "passive"))
      (node (ref "R2") (pin "2") (pinfunction "2_2") (pintype "passive"))
      (node (ref "R7") (pin "1") (pinfunction "1_1") (pintype "passive"))
      (node (ref "R8") (pin "2") (pinfunction "2_2") (pintype "passive"))
      (node (ref "SV3") (pin "8") (pinfunction "8_8") (pintype "passive"))
    )
    (net (code "2") (name "/1") (class "Default")
      (node (ref "D1") (pin "C") (pinfunction "C_C") (pintype "passive"))
      (node (ref "D3") (pin "C") (pinfunction "C_C") (pintype "passive"))
      (node (ref "J19") (pin "2") (pinfunction "P$2_2") (pintype "bidirectional"))
      (node (ref "J32") (pin "1") (pinfunction "P$1_1") (pintype "bidirectional"))
    )
    (net (code "3") (name "/1J") (class "Default")
      (node (ref "D5") (pin "C") (pinfunction "C_C") (pintype "passive"))
      (node (ref "J19") (pin "1") (pinfunction "P$1_1") (pintype "bidirectional"))
      (node (ref "J20") (pin "1") (pinfunction "P$1_1") (pintype "bidirectional"))
    )
    (net (code "4") (name "/1J2") (class "Default")
      (node (ref "D7") (pin "C") (pinfunction "C_C") (pintype "passive"))
      (node (ref "J20") (pin "2") (pinfunction "P$2_2") (pintype "bidirectional"))
      (node (ref "J21") (pin "1") (pinfunction "P$1_1") (pintype "bidirectional"))
    )
    (net (code "5") (name "/1J3") (class "Default")
      (node (ref "D10") (pin "C") (pinfunction "C_C") (pintype "passive"))
      (node (ref "J21") (pin "2") (pinfunction "P$2_2") (pintype "bidirectional"))
    )
    (net (code "6") (name "/2") (class "Default")
      (node (ref "D2") (pin "C") (pinfunction "C_C") (pintype "passive"))
      (node (ref "D4") (pin "C") (pinfunction "C_C") (pintype "passive"))
      (node (ref "J16") (pin "2") (pinfunction "P$2_2") (pintype "bidirectional"))
      (node (ref "J33") (pin "1") (pinfunction "P$1_1") (pintype "bidirectional"))
    )
    (net (code "7") (name "/2J") (class "Default")
      (node (ref "D6") (pin "C") (pinfunction "C_C") (pintype "passive"))
      (node (ref "J16") (pin "1") (pinfunction "P$1_1") (pintype "bidirectional"))
      (node (ref "J17") (pin "1") (pinfunction "P$1_1") (pintype "bidirectional"))
    )
    (net (code "8") (name "/2J2") (class "Default")
      (node (ref "D37") (pin "C") (pinfunction "C_C") (pintype "passive"))
      (node (ref "D8") (pin "C") (pinfunction "C_C") (pintype "passive"))
      (node (ref "D9") (pin "C") (pinfunction "C_C") (pintype "passive"))
      (node (ref "J17") (pin "2") (pinfunction "P$2_2") (pintype "bidirectional"))
    )
    (net (code "9") (name "/3") (class "Default")
      (node (ref "D13") (pin "C") (pinfunction "C_C") (pintype "passive"))
      (node (ref "D88") (pin "C") (pinfunction "C_C") (pintype "passive"))
      (node (ref "J13") (pin "2") (pinfunction "P$2_2") (pintype "bidirectional"))
      (node (ref "J34") (pin "1") (pinfunction "P$1_1") (pintype "bidirectional"))
    )
    (net (code "10") (name "/3J") (class "Default")
      (node (ref "D25") (pin "C") (pinfunction "C_C") (pintype "passive"))
      (node (ref "J13") (pin "1") (pinfunction "P$1_1") (pintype "bidirectional"))
      (node (ref "J14") (pin "1") (pinfunction "P$1_1") (pintype "bidirectional"))
    )
    (net (code "11") (name "/3J2") (class "Default")
      (node (ref "D31") (pin "C") (pinfunction "C_C") (pintype "passive"))
      (node (ref "J14") (pin "2") (pinfunction "P$2_2") (pintype "bidirectional"))
      (node (ref "J15") (pin "1") (pinfunction "P$1_1") (pintype "bidirectional"))
    )
    (net (code "12") (name "/3J3") (class "Default")
      (node (ref "D11") (pin "C") (pinfunction "C_C") (pintype "passive"))
      (node (ref "D38") (pin "C") (pinfunction "C_C") (pintype "passive"))
      (node (ref "J15") (pin "2") (pinfunction "P$2_2") (pintype "bidirectional"))
    )
    (net (code "13") (name "/4") (class "Default")
      (node (ref "D14") (pin "C") (pinfunction "C_C") (pintype "passive"))
      (node (ref "D19") (pin "C") (pinfunction "C_C") (pintype "passive"))
      (node (ref "J10") (pin "2") (pinfunction "P$2_2") (pintype "bidirectional"))
      (node (ref "J25") (pin "1") (pinfunction "P$1_1") (pintype "bidirectional"))
    )
    (net (code "14") (name "/4J") (class "Default")
      (node (ref "D26") (pin "C") (pinfunction "C_C") (pintype "passive"))
      (node (ref "J10") (pin "1") (pinfunction "P$1_1") (pintype "bidirectional"))
      (node (ref "J11") (pin "1") (pinfunction "P$1_1") (pintype "bidirectional"))
    )
    (net (code "15") (name "/4J2") (class "Default")
      (node (ref "D32") (pin "C") (pinfunction "C_C") (pintype "passive"))
      (node (ref "J11") (pin "2") (pinfunction "P$2_2") (pintype "bidirectional"))
      (node (ref "J12") (pin "1") (pinfunction "P$1_1") (pintype "bidirectional"))
    )
    (net (code "16") (name "/4J3") (class "Default")
      (node (ref "D12") (pin "C") (pinfunction "C_C") (pintype "passive"))
      (node (ref "D39") (pin "C") (pinfunction "C_C") (pintype "passive"))
      (node (ref "J12") (pin "2") (pinfunction "P$2_2") (pintype "bidirectional"))
    )
    (net (code "17") (name "/5") (class "Default")
      (node (ref "1D1") (pin "14") (pinfunction "Y1_14") (pintype "output"))
      (node (ref "D15") (pin "C") (pinfunction "C_C") (pintype "passive"))
      (node (ref "D20") (pin "C") (pinfunction "C_C") (pintype "passive"))
      (node (ref "J7") (pin "2") (pinfunction "P$2_2") (pintype "bidirectional"))
    )
    (net (code "18") (name "/5J") (class "Default")
      (node (ref "D27") (pin "C") (pinfunction "C_C") (pintype "passive"))
      (node (ref "J7") (pin "1") (pinfunction "P$1_1") (pintype "bidirectional"))
      (node (ref "J8") (pin "1") (pinfunction "P$1_1") (pintype "bidirectional"))
    )
    (net (code "19") (name "/5J2") (class "Default")
      (node (ref "D33") (pin "C") (pinfunction "C_C") (pintype "passive"))
      (node (ref "J8") (pin "2") (pinfunction "P$2_2") (pintype "bidirectional"))
      (node (ref "J9") (pin "1") (pinfunction "P$1_1") (pintype "bidirectional"))
    )
    (net (code "20") (name "/5J3") (class "Default")
      (node (ref "D40") (pin "C") (pinfunction "C_C") (pintype "passive"))
      (node (ref "D43") (pin "C") (pinfunction "C_C") (pintype "passive"))
      (node (ref "J9") (pin "2") (pinfunction "P$2_2") (pintype "bidirectional"))
    )
    (net (code "21") (name "/6") (class "Default")
      (node (ref "1D1") (pin "7") (pinfunction "Y7_7") (pintype "output"))
      (node (ref "D16") (pin "C") (pinfunction "C_C") (pintype "passive"))
      (node (ref "D21") (pin "C") (pinfunction "C_C") (pintype "passive"))
      (node (ref "J4") (pin "2") (pinfunction "P$2_2") (pintype "bidirectional"))
    )
    (net (code "22") (name "/6J") (class "Default")
      (node (ref "D28") (pin "C") (pinfunction "C_C") (pintype "passive"))
      (node (ref "J4") (pin "1") (pinfunction "P$1_1") (pintype "bidirectional"))
      (node (ref "J5") (pin "1") (pinfunction "P$1_1") (pintype "bidirectional"))
    )
    (net (code "23") (name "/6J2") (class "Default")
      (node (ref "D34") (pin "C") (pinfunction "C_C") (pintype "passive"))
      (node (ref "J5") (pin "2") (pinfunction "P$2_2") (pintype "bidirectional"))
      (node (ref "J6") (pin "2") (pinfunction "P$2_2") (pintype "bidirectional"))
    )
    (net (code "24") (name "/6J3") (class "Default")
      (node (ref "D41") (pin "C") (pinfunction "C_C") (pintype "passive"))
      (node (ref "D44") (pin "C") (pinfunction "C_C") (pintype "passive"))
      (node (ref "J6") (pin "1") (pinfunction "P$1_1") (pintype "bidirectional"))
    )
    (net (code "25") (name "/7") (class "Default")
      (node (ref "D22") (pin "C") (pinfunction "C_C") (pintype "passive"))
      (node (ref "D29") (pin "C") (pinfunction "C_C") (pintype "passive"))
      (node (ref "J1") (pin "2") (pinfunction "P$2_2") (pintype "bidirectional"))
      (node (ref "J2") (pin "1") (pinfunction "P$1_1") (pintype "bidirectional"))
    )
    (net (code "26") (name "/7J") (class "Default")
      (node (ref "1D1") (pin "10") (pinfunction "Y5_10") (pintype "output"))
      (node (ref "D17") (pin "C") (pinfunction "C_C") (pintype "passive"))
      (node (ref "J1") (pin "1") (pinfunction "P$1_1") (pintype "bidirectional"))
    )
    (net (code "27") (name "/7J2") (class "Default")
      (node (ref "D35") (pin "C") (pinfunction "C_C") (pintype "passive"))
      (node (ref "J2") (pin "2") (pinfunction "P$2_2") (pintype "bidirectional"))
      (node (ref "J3") (pin "2") (pinfunction "P$2_2") (pintype "bidirectional"))
    )
    (net (code "28") (name "/7J3") (class "Default")
      (node (ref "D42") (pin "C") (pinfunction "C_C") (pintype "passive"))
      (node (ref "D45") (pin "C") (pinfunction "C_C") (pintype "passive"))
      (node (ref "J3") (pin "1") (pinfunction "P$1_1") (pintype "bidirectional"))
    )
    (net (code "29") (name "/8") (class "Default")
      (node (ref "1D1") (pin "9") (pinfunction "Y6_9") (pintype "output"))
      (node (ref "D18") (pin "C") (pinfunction "C_C") (pintype "passive"))
      (node (ref "D23") (pin "C") (pinfunction "C_C") (pintype "passive"))
      (node (ref "D24") (pin "C") (pinfunction "C_C") (pintype "passive"))
      (node (ref "D30") (pin "C") (pinfunction "C_C") (pintype "passive"))
      (node (ref "D36") (pin "C") (pinfunction "C_C") (pintype "passive"))
      (node (ref "D46") (pin "C") (pinfunction "C_C") (pintype "passive"))
    )
    (net (code "30") (name "/AFN1A") (class "Default")
      (node (ref "JB44") (pin "2") (pinfunction "2_2") (pintype "passive"))
      (node (ref "S44") (pin "SW1") (pinfunction "PIN-1_SW1") (pintype "passive"))
      (node (ref "S44A") (pin "SW1") (pinfunction "PIN-1_SW1") (pintype "passive"))
    )
    (net (code "31") (name "/AFN1B") (class "Default")
      (node (ref "JA44") (pin "1") (pinfunction "1_1") (pintype "passive"))
      (node (ref "S44") (pin "SW2") (pinfunction "PIN-2_SW2") (pintype "passive"))
      (node (ref "S44A") (pin "SW2") (pinfunction "PIN-2_SW2") (pintype "passive"))
    )
    (net (code "32") (name "/D1") (class "Default")
      (node (ref "J38") (pin "2") (pinfunction "P$2_2") (pintype "bidirectional"))
      (node (ref "SV1") (pin "1") (pinfunction "1_1") (pintype "passive"))
    )
    (net (code "33") (name "/D2") (class "Default")
      (node (ref "J39") (pin "2") (pinfunction "P$2_2") (pintype "bidirectional"))
      (node (ref "SV1") (pin "2") (pinfunction "2_2") (pintype "passive"))
    )
    (net (code "34") (name "/D3") (class "Default")
      (node (ref "J40") (pin "2") (pinfunction "P$2_2") (pintype "bidirectional"))
      (node (ref "SV1") (pin "3") (pinfunction "3_3") (pintype "passive"))
    )
    (net (code "35") (name "/L1") (class "Default")
      (node (ref "1D2") (pin "11") (pinfunction "I_11") (pintype "input"))
      (node (ref "JA1") (pin "2") (pinfunction "2_2") (pintype "passive"))
      (node (ref "JA13") (pin "2") (pinfunction "2_2") (pintype "passive"))
      (node (ref "JA14") (pin "2") (pinfunction "2_2") (pintype "passive"))
      (node (ref "JA15") (pin "2") (pinfunction "2_2") (pintype "passive"))
      (node (ref "JA16") (pin "2") (pinfunction "2_2") (pintype "passive"))
      (node (ref "JA17") (pin "2") (pinfunction "2_2") (pintype "passive"))
      (node (ref "JA18") (pin "2") (pinfunction "2_2") (pintype "passive"))
      (node (ref "JA2") (pin "2") (pinfunction "2_2") (pintype "passive"))
      (node (ref "R7") (pin "2") (pinfunction "2_2") (pintype "passive"))
    )
    (net (code "36") (name "/L2") (class "Default")
      (node (ref "J42") (pin "2") (pinfunction "P$2_2") (pintype "bidirectional"))
      (node (ref "JA19") (pin "2") (pinfunction "2_2") (pintype "passive"))
      (node (ref "JA20") (pin "2") (pinfunction "2_2") (pintype "passive"))
      (node (ref "JA21") (pin "2") (pinfunction "2_2") (pintype "passive"))
      (node (ref "JA22") (pin "2") (pinfunction "2_2") (pintype "passive"))
      (node (ref "JA23") (pin "2") (pinfunction "2_2") (pintype "passive"))
      (node (ref "JA3") (pin "2") (pinfunction "2_2") (pintype "passive"))
      (node (ref "JA4") (pin "2") (pinfunction "2_2") (pintype "passive"))
      (node (ref "JA88") (pin "2") (pinfunction "2_2") (pintype "passive"))
    )
    (net (code "37") (name "/L2J1") (class "Default")
      (node (ref "J42") (pin "1") (pinfunction "P$1_1") (pintype "bidirectional"))
      (node (ref "J44") (pin "2") (pinfunction "P$2_2") (pintype "bidirectional"))
    )
    (net (code "38") (name "/L2J3") (class "Default")
      (node (ref "1D2") (pin "1") (pinfunction "I_1") (pintype "input"))
      (node (ref "J44") (pin "1") (pinfunction "P$1_1") (pintype "bidirectional"))
      (node (ref "R4") (pin "2") (pinfunction "2_2") (pintype "passive"))
    )
    (net (code "39") (name "/L3") (class "Default")
      (node (ref "J47") (pin "2") (pinfunction "P$2_2") (pintype "bidirectional"))
      (node (ref "JA24") (pin "2") (pinfunction "2_2") (pintype "passive"))
      (node (ref "JA25") (pin "2") (pinfunction "2_2") (pintype "passive"))
      (node (ref "JA26") (pin "2") (pinfunction "2_2") (pintype "passive"))
      (node (ref "JA27") (pin "2") (pinfunction "2_2") (pintype "passive"))
      (node (ref "JA28") (pin "2") (pinfunction "2_2") (pintype "passive"))
      (node (ref "JA29") (pin "2") (pinfunction "2_2") (pintype "passive"))
    )
    (net (code "40") (name "/L3J") (class "Default")
      (node (ref "J45") (pin "2") (pinfunction "P$2_2") (pintype "bidirectional"))
      (node (ref "J49") (pin "1") (pinfunction "P$1_1") (pintype "bidirectional"))
      (node (ref "JA5") (pin "2") (pinfunction "2_2") (pintype "passive"))
      (node (ref "JA6") (pin "2") (pinfunction "2_2") (pintype "passive"))
    )
    (net (code "41") (name "/L3J1") (class "Default")
      (node (ref "J47") (pin "1") (pinfunction "P$1_1") (pintype "bidirectional"))
      (node (ref "J48") (pin "2") (pinfunction "P$2_2") (pintype "bidirectional"))
      (node (ref "R2") (pin "1") (pinfunction "1_1") (pintype "passive"))
    )
    (net (code "42") (name "/L4") (class "Default")
      (node (ref "1D2") (pin "9") (pinfunction "I_9") (pintype "input"))
      (node (ref "JA30") (pin "2") (pinfunction "2_2") (pintype "passive"))
      (node (ref "JA31") (pin "2") (pinfunction "2_2") (pintype "passive"))
      (node (ref "JA32") (pin "2") (pinfunction "2_2") (pintype "passive"))
      (node (ref "JA33") (pin "2") (pinfunction "2_2") (pintype "passive"))
      (node (ref "JA34") (pin "2") (pinfunction "2_2") (pintype "passive"))
      (node (ref "JA35") (pin "2") (pinfunction "2_2") (pintype "passive"))
      (node (ref "JA7") (pin "2") (pinfunction "2_2") (pintype "passive"))
      (node (ref "JA8") (pin "2") (pinfunction "2_2") (pintype "passive"))
      (node (ref "R8") (pin "1") (pinfunction "1_1") (pintype "passive"))
    )
    (net (code "43") (name "/L5") (class "Default")
      (node (ref "1D2") (pin "5") (pinfunction "I_5") (pintype "input"))
      (node (ref "JA36") (pin "2") (pinfunction "2_2") (pintype "passive"))
      (node (ref "JA37") (pin "2") (pinfunction "2_2") (pintype "passive"))
      (node (ref "JA38") (pin "2") (pinfunction "2_2") (pintype "passive"))
      (node (ref "JA39") (pin "2") (pinfunction "2_2") (pintype "passive"))
      (node (ref "JA40") (pin "2") (pinfunction "2_2") (pintype "passive"))
      (node (ref "JA41") (pin "2") (pinfunction "2_2") (pintype "passive"))
      (node (ref "JA42") (pin "2") (pinfunction "2_2") (pintype "passive"))
      (node (ref "R6") (pin "2") (pinfunction "2_2") (pintype "passive"))
    )
    (net (code "44") (name "/L6") (class "Default")
      (node (ref "1D2") (pin "3") (pinfunction "I_3") (pintype "input"))
      (node (ref "JA10") (pin "2") (pinfunction "2_2") (pintype "passive"))
      (node (ref "JA11") (pin "2") (pinfunction "2_2") (pintype "passive"))
      (node (ref "JA12") (pin "2") (pinfunction "2_2") (pintype "passive"))
      (node (ref "JA43") (pin "2") (pinfunction "2_2") (pintype "passive"))
      (node (ref "JA44") (pin "2") (pinfunction "2_2") (pintype "passive"))
      (node (ref "JA45") (pin "2") (pinfunction "2_2") (pintype "passive"))
      (node (ref "JA46") (pin "2") (pinfunction "2_2") (pintype "passive"))
      (node (ref "JA9") (pin "2") (pinfunction "2_2") (pintype "passive"))
      (node (ref "R5") (pin "2") (pinfunction "2_2") (pintype "passive"))
    )
    (net (code "45") (name "/N$63") (class "Default")
      (node (ref "JB43") (pin "2") (pinfunction "2_2") (pintype "passive"))
      (node (ref "S43") (pin "SW1") (pinfunction "PIN-1_SW1") (pintype "passive"))
      (node (ref "S44A1") (pin "SW1") (pinfunction "PIN-1_SW1") (pintype "passive"))
    )
    (net (code "46") (name "/N$113") (class "Default")
      (node (ref "JA43") (pin "1") (pinfunction "1_1") (pintype "passive"))
      (node (ref "S43") (pin "SW2") (pinfunction "PIN-2_SW2") (pintype "passive"))
      (node (ref "S44A1") (pin "SW2") (pinfunction "PIN-2_SW2") (pintype "passive"))
    )
    (net (code "47") (name "/N$193") (class "Default")
      (node (ref "1D2") (pin "13") (pinfunction "I_13") (pintype "input"))
      (node (ref "J45") (pin "1") (pinfunction "P$1_1") (pintype "bidirectional"))
    )
    (net (code "48") (name "/N$195") (class "Default")
      (node (ref "J53") (pin "1") (pinfunction "P$1_1") (pintype "bidirectional"))
      (node (ref "SV3") (pin "4") (pinfunction "4_4") (pintype "passive"))
    )
    (net (code "49") (name "/N$196") (class "Default")
      (node (ref "J51") (pin "1") (pinfunction "P$1_1") (pintype "bidirectional"))
      (node (ref "SV3") (pin "5") (pinfunction "5_5") (pintype "passive"))
    )
    (net (code "50") (name "/N$198") (class "Default")
      (node (ref "J55") (pin "1") (pinfunction "P$1_1") (pintype "bidirectional"))
      (node (ref "SV3") (pin "3") (pinfunction "3_3") (pintype "passive"))
    )
    (net (code "51") (name "/N$199") (class "Default")
      (node (ref "J57") (pin "1") (pinfunction "P$1_1") (pintype "bidirectional"))
      (node (ref "SV3") (pin "2") (pinfunction "2_2") (pintype "passive"))
    )
    (net (code "52") (name "/N$200") (class "Default")
      (node (ref "J18") (pin "1") (pinfunction "P$1_1") (pintype "bidirectional"))
      (node (ref "SV3") (pin "7") (pinfunction "7_7") (pintype "passive"))
    )
    (net (code "53") (name "/N$203") (class "Default")
      (node (ref "J46") (pin "1") (pinfunction "P$1_1") (pintype "bidirectional"))
      (node (ref "SV3") (pin "6") (pinfunction "6_6") (pintype "passive"))
    )
    (net (code "54") (name "/VCCD2") (class "Default")
      (node (ref "1D2") (pin "14") (pinfunction "VCC_14") (pintype "power_in"))
      (node (ref "C18") (pin "2") (pinfunction "2_2") (pintype "passive"))
      (node (ref "D47") (pin "C") (pinfunction "C_C") (pintype "passive"))
      (node (ref "R3") (pin "1") (pinfunction "1_1") (pintype "passive"))
      (node (ref "R4") (pin "1") (pinfunction "1_1") (pintype "passive"))
      (node (ref "R5") (pin "1") (pinfunction "1_1") (pintype "passive"))
    )
    (net (code "55") (name "GND") (class "Default")
      (node (ref "1D1") (pin "4") (pinfunction "G2A_4") (pintype "input"))
      (node (ref "1D1") (pin "5") (pinfunction "G2B_5") (pintype "input"))
      (node (ref "1D1") (pin "8") (pinfunction "GND_8") (pintype "power_in"))
      (node (ref "1D2") (pin "7") (pinfunction "GND_7") (pintype "power_in"))
      (node (ref "C17") (pin "1") (pinfunction "1_1") (pintype "passive"))
      (node (ref "C18") (pin "1") (pinfunction "1_1") (pintype "passive"))
      (node (ref "SV3") (pin "1") (pinfunction "1_1") (pintype "passive"))
    )
    (net (code "56") (name "Net-(1D1A-A)") (class "Default")
      (node (ref "1D1") (pin "1") (pinfunction "A_1") (pintype "input"))
      (node (ref "J27") (pin "1") (pinfunction "P$1_1") (pintype "bidirectional"))
    )
    (net (code "57") (name "Net-(1D1A-B)") (class "Default")
      (node (ref "1D1") (pin "2") (pinfunction "B_2") (pintype "input"))
      (node (ref "J28") (pin "1") (pinfunction "P$1_1") (pintype "bidirectional"))
    )
    (net (code "58") (name "Net-(1D1A-C)") (class "Default")
      (node (ref "1D1") (pin "3") (pinfunction "C_3") (pintype "input"))
      (node (ref "J29") (pin "1") (pinfunction "P$1_1") (pintype "bidirectional"))
    )
    (net (code "59") (name "Net-(1D1A-G1)") (class "Default")
      (node (ref "1D1") (pin "6") (pinfunction "G1_6") (pintype "input"))
      (node (ref "R1") (pin "2") (pinfunction "2_2") (pintype "passive"))
    )
    (net (code "60") (name "Net-(1D1A-Y0)") (class "Default")
      (node (ref "1D1") (pin "15") (pinfunction "Y0_15") (pintype "output"))
      (node (ref "J43") (pin "2") (pinfunction "P$2_2") (pintype "bidirectional"))
    )
    (net (code "61") (name "Net-(1D1A-Y2)") (class "Default")
      (node (ref "1D1") (pin "13") (pinfunction "Y2_13") (pintype "output"))
      (node (ref "J24") (pin "2") (pinfunction "P$2_2") (pintype "bidirectional"))
    )
    (net (code "62") (name "Net-(1D1A-Y3)") (class "Default")
      (node (ref "1D1") (pin "12") (pinfunction "Y3_12") (pintype "output"))
      (node (ref "J26") (pin "2") (pinfunction "P$2_2") (pintype "bidirectional"))
    )
    (net (code "63") (name "Net-(1D1A-Y4)") (class "Default")
      (node (ref "1D1") (pin "11") (pinfunction "Y4_11") (pintype "output"))
      (node (ref "J41") (pin "2") (pinfunction "P$2_2") (pintype "bidirectional"))
    )
    (net (code "64") (name "Net-(1D2A-O)") (class "Default")
      (node (ref "1D2") (pin "2") (pinfunction "O_2") (pintype "output"))
      (node (ref "J52") (pin "2") (pinfunction "P$2_2") (pintype "bidirectional"))
    )
    (net (code "65") (name "Net-(1D2B-O)") (class "Default")
      (node (ref "1D2") (pin "4") (pinfunction "O_4") (pintype "output"))
      (node (ref "J54") (pin "2") (pinfunction "P$2_2") (pintype "bidirectional"))
    )
    (net (code "66") (name "Net-(1D2C-O)") (class "Default")
      (node (ref "1D2") (pin "6") (pinfunction "O_6") (pintype "output"))
      (node (ref "J56") (pin "2") (pinfunction "P$2_2") (pintype "bidirectional"))
    )
    (net (code "67") (name "Net-(1D2D-O)") (class "Default")
      (node (ref "1D2") (pin "8") (pinfunction "O_8") (pintype "output"))
      (node (ref "J18") (pin "2") (pinfunction "P$2_2") (pintype "bidirectional"))
    )
    (net (code "68") (name "Net-(1D2E-O)") (class "Default")
      (node (ref "1D2") (pin "10") (pinfunction "O_10") (pintype "output"))
      (node (ref "J23") (pin "2") (pinfunction "P$2_2") (pintype "bidirectional"))
    )
    (net (code "69") (name "Net-(1D2F-O)") (class "Default")
      (node (ref "1D2") (pin "12") (pinfunction "O_12") (pintype "output"))
      (node (ref "J50") (pin "2") (pinfunction "P$2_2") (pintype "bidirectional"))
    )
    (net (code "70") (name "Net-(D1-PadA)") (class "Default")
      (node (ref "D1") (pin "A") (pinfunction "A_A") (pintype "passive"))
      (node (ref "JB1") (pin "1") (pinfunction "1_1") (pintype "passive"))
    )
    (net (code "71") (name "Net-(D2-PadA)") (class "Default")
      (node (ref "D2") (pin "A") (pinfunction "A_A") (pintype "passive"))
      (node (ref "JB2") (pin "1") (pinfunction "1_1") (pintype "passive"))
    )
    (net (code "72") (name "Net-(D3-PadA)") (class "Default")
      (node (ref "D3") (pin "A") (pinfunction "A_A") (pintype "passive"))
      (node (ref "JB3") (pin "1") (pinfunction "1_1") (pintype "passive"))
    )
    (net (code "73") (name "Net-(D4-PadA)") (class "Default")
      (node (ref "D4") (pin "A") (pinfunction "A_A") (pintype "passive"))
      (node (ref "JB4") (pin "1") (pinfunction "1_1") (pintype "passive"))
    )
    (net (code "74") (name "Net-(D5-PadA)") (class "Default")
      (node (ref "D5") (pin "A") (pinfunction "A_A") (pintype "passive"))
      (node (ref "JB5") (pin "1") (pinfunction "1_1") (pintype "passive"))
    )
    (net (code "75") (name "Net-(D6-PadA)") (class "Default")
      (node (ref "D6") (pin "A") (pinfunction "A_A") (pintype "passive"))
      (node (ref "JB6") (pin "1") (pinfunction "1_1") (pintype "passive"))
    )
    (net (code "76") (name "Net-(D7-PadA)") (class "Default")
      (node (ref "D7") (pin "A") (pinfunction "A_A") (pintype "passive"))
      (node (ref "JB7") (pin "1") (pinfunction "1_1") (pintype "passive"))
    )
    (net (code "77") (name "Net-(D8-PadA)") (class "Default")
      (node (ref "D8") (pin "A") (pinfunction "A_A") (pintype "passive"))
      (node (ref "JB8") (pin "1") (pinfunction "1_1") (pintype "passive"))
    )
    (net (code "78") (name "Net-(D9-PadA)") (class "Default")
      (node (ref "D9") (pin "A") (pinfunction "A_A") (pintype "passive"))
      (node (ref "JB9") (pin "1") (pinfunction "1_1") (pintype "passive"))
    )
    (net (code "79") (name "Net-(D10-PadA)") (class "Default")
      (node (ref "D10") (pin "A") (pinfunction "A_A") (pintype "passive"))
      (node (ref "JB10") (pin "1") (pinfunction "1_1") (pintype "passive"))
    )
    (net (code "80") (name "Net-(D11-PadA)") (class "Default")
      (node (ref "D11") (pin "A") (pinfunction "A_A") (pintype "passive"))
      (node (ref "JB11") (pin "1") (pinfunction "1_1") (pintype "passive"))
    )
    (net (code "81") (name "Net-(D12-PadA)") (class "Default")
      (node (ref "D12") (pin "A") (pinfunction "A_A") (pintype "passive"))
      (node (ref "JB12") (pin "1") (pinfunction "1_1") (pintype "passive"))
    )
    (net (code "82") (name "Net-(D13-PadA)") (class "Default")
      (node (ref "D13") (pin "A") (pinfunction "A_A") (pintype "passive"))
      (node (ref "JB13") (pin "1") (pinfunction "1_1") (pintype "passive"))
    )
    (net (code "83") (name "Net-(D14-PadA)") (class "Default")
      (node (ref "D14") (pin "A") (pinfunction "A_A") (pintype "passive"))
      (node (ref "JB14") (pin "1") (pinfunction "1_1") (pintype "passive"))
    )
    (net (code "84") (name "Net-(D15-PadA)") (class "Default")
      (node (ref "D15") (pin "A") (pinfunction "A_A") (pintype "passive"))
      (node (ref "JB15") (pin "1") (pinfunction "1_1") (pintype "passive"))
    )
    (net (code "85") (name "Net-(D16-PadA)") (class "Default")
      (node (ref "D16") (pin "A") (pinfunction "A_A") (pintype "passive"))
      (node (ref "JB16") (pin "1") (pinfunction "1_1") (pintype "passive"))
    )
    (net (code "86") (name "Net-(D17-PadA)") (class "Default")
      (node (ref "D17") (pin "A") (pinfunction "A_A") (pintype "passive"))
      (node (ref "JB17") (pin "1") (pinfunction "1_1") (pintype "passive"))
    )
    (net (code "87") (name "Net-(D18-PadA)") (class "Default")
      (node (ref "D18") (pin "A") (pinfunction "A_A") (pintype "passive"))
      (node (ref "JB18") (pin "1") (pinfunction "1_1") (pintype "passive"))
    )
    (net (code "88") (name "Net-(D19-PadA)") (class "Default")
      (node (ref "D19") (pin "A") (pinfunction "A_A") (pintype "passive"))
      (node (ref "JB19") (pin "1") (pinfunction "1_1") (pintype "passive"))
    )
    (net (code "89") (name "Net-(D20-PadA)") (class "Default")
      (node (ref "D20") (pin "A") (pinfunction "A_A") (pintype "passive"))
      (node (ref "JB20") (pin "1") (pinfunction "1_1") (pintype "passive"))
    )
    (net (code "90") (name "Net-(D21-PadA)") (class "Default")
      (node (ref "D21") (pin "A") (pinfunction "A_A") (pintype "passive"))
      (node (ref "JB21") (pin "1") (pinfunction "1_1") (pintype "passive"))
    )
    (net (code "91") (name "Net-(D22-PadA)") (class "Default")
      (node (ref "D22") (pin "A") (pinfunction "A_A") (pintype "passive"))
      (node (ref "JB22") (pin "1") (pinfunction "1_1") (pintype "passive"))
    )
    (net (code "92") (name "Net-(D23-PadA)") (class "Default")
      (node (ref "D23") (pin "A") (pinfunction "A_A") (pintype "passive"))
      (node (ref "JB23") (pin "1") (pinfunction "1_1") (pintype "passive"))
    )
    (net (code "93") (name "Net-(D24-PadA)") (class "Default")
      (node (ref "D24") (pin "A") (pinfunction "A_A") (pintype "passive"))
      (node (ref "JB24") (pin "1") (pinfunction "1_1") (pintype "passive"))
    )
    (net (code "94") (name "Net-(D25-PadA)") (class "Default")
      (node (ref "D25") (pin "A") (pinfunction "A_A") (pintype "passive"))
      (node (ref "JB25") (pin "1") (pinfunction "1_1") (pintype "passive"))
    )
    (net (code "95") (name "Net-(D26-PadA)") (class "Default")
      (node (ref "D26") (pin "A") (pinfunction "A_A") (pintype "passive"))
      (node (ref "JB26") (pin "1") (pinfunction "1_1") (pintype "passive"))
    )
    (net (code "96") (name "Net-(D27-PadA)") (class "Default")
      (node (ref "D27") (pin "A") (pinfunction "A_A") (pintype "passive"))
      (node (ref "JB27") (pin "1") (pinfunction "1_1") (pintype "passive"))
    )
    (net (code "97") (name "Net-(D28-PadA)") (class "Default")
      (node (ref "D28") (pin "A") (pinfunction "A_A") (pintype "passive"))
      (node (ref "JB28") (pin "1") (pinfunction "1_1") (pintype "passive"))
    )
    (net (code "98") (name "Net-(D29-PadA)") (class "Default")
      (node (ref "D29") (pin "A") (pinfunction "A_A") (pintype "passive"))
      (node (ref "JB29") (pin "1") (pinfunction "1_1") (pintype "passive"))
    )
    (net (code "99") (name "Net-(D30-PadA)") (class "Default")
      (node (ref "D30") (pin "A") (pinfunction "A_A") (pintype "passive"))
      (node (ref "JB30") (pin "1") (pinfunction "1_1") (pintype "passive"))
    )
    (net (code "100") (name "Net-(D31-PadA)") (class "Default")
      (node (ref "D31") (pin "A") (pinfunction "A_A") (pintype "passive"))
      (node (ref "JB31") (pin "1") (pinfunction "1_1") (pintype "passive"))
    )
    (net (code "101") (name "Net-(D32-PadA)") (class "Default")
      (node (ref "D32") (pin "A") (pinfunction "A_A") (pintype "passive"))
      (node (ref "JB32") (pin "1") (pinfunction "1_1") (pintype "passive"))
    )
    (net (code "102") (name "Net-(D33-PadA)") (class "Default")
      (node (ref "D33") (pin "A") (pinfunction "A_A") (pintype "passive"))
      (node (ref "JB33") (pin "1") (pinfunction "1_1") (pintype "passive"))
    )
    (net (code "103") (name "Net-(D34-PadA)") (class "Default")
      (node (ref "D34") (pin "A") (pinfunction "A_A") (pintype "passive"))
      (node (ref "JB34") (pin "1") (pinfunction "1_1") (pintype "passive"))
    )
    (net (code "104") (name "Net-(D35-PadA)") (class "Default")
      (node (ref "D35") (pin "A") (pinfunction "A_A") (pintype "passive"))
      (node (ref "JB35") (pin "1") (pinfunction "1_1") (pintype "passive"))
    )
    (net (code "105") (name "Net-(D36-PadA)") (class "Default")
      (node (ref "D36") (pin "A") (pinfunction "A_A") (pintype "passive"))
      (node (ref "JB36") (pin "1") (pinfunction "1_1") (pintype "passive"))
    )
    (net (code "106") (name "Net-(D37-PadA)") (class "Default")
      (node (ref "D37") (pin "A") (pinfunction "A_A") (pintype "passive"))
      (node (ref "JB37") (pin "1") (pinfunction "1_1") (pintype "passive"))
    )
    (net (code "107") (name "Net-(D38-PadA)") (class "Default")
      (node (ref "D38") (pin "A") (pinfunction "A_A") (pintype "passive"))
      (node (ref "JB38") (pin "1") (pinfunction "1_1") (pintype "passive"))
    )
    (net (code "108") (name "Net-(D39-PadA)") (class "Default")
      (node (ref "D39") (pin "A") (pinfunction "A_A") (pintype "passive"))
      (node (ref "JB39") (pin "1") (pinfunction "1_1") (pintype "passive"))
    )
    (net (code "109") (name "Net-(D40-PadA)") (class "Default")
      (node (ref "D40") (pin "A") (pinfunction "A_A") (pintype "passive"))
      (node (ref "JB40") (pin "1") (pinfunction "1_1") (pintype "passive"))
    )
    (net (code "110") (name "Net-(D41-PadA)") (class "Default")
      (node (ref "D41") (pin "A") (pinfunction "A_A") (pintype "passive"))
      (node (ref "JB41") (pin "1") (pinfunction "1_1") (pintype "passive"))
    )
    (net (code "111") (name "Net-(D42-PadA)") (class "Default")
      (node (ref "D42") (pin "A") (pinfunction "A_A") (pintype "passive"))
      (node (ref "JB42") (pin "1") (pinfunction "1_1") (pintype "passive"))
    )
    (net (code "112") (name "Net-(D43-PadA)") (class "Default")
      (node (ref "D43") (pin "A") (pinfunction "A_A") (pintype "passive"))
      (node (ref "JB43") (pin "1") (pinfunction "1_1") (pintype "passive"))
    )
    (net (code "113") (name "Net-(D44-PadA)") (class "Default")
      (node (ref "D44") (pin "A") (pinfunction "A_A") (pintype "passive"))
      (node (ref "JB44") (pin "1") (pinfunction "1_1") (pintype "passive"))
    )
    (net (code "114") (name "Net-(D45-PadA)") (class "Default")
      (node (ref "D45") (pin "A") (pinfunction "A_A") (pintype "passive"))
      (node (ref "JB45") (pin "1") (pinfunction "1_1") (pintype "passive"))
    )
    (net (code "115") (name "Net-(D46-PadA)") (class "Default")
      (node (ref "D46") (pin "A") (pinfunction "A_A") (pintype "passive"))
      (node (ref "JB46") (pin "1") (pinfunction "1_1") (pintype "passive"))
    )
    (net (code "116") (name "Net-(D47-PadA)") (class "Default")
      (node (ref "D47") (pin "A") (pinfunction "A_A") (pintype "passive"))
      (node (ref "D48") (pin "C") (pinfunction "C_C") (pintype "passive"))
    )
    (net (code "117") (name "Net-(D88-PadA)") (class "Default")
      (node (ref "D88") (pin "A") (pinfunction "A_A") (pintype "passive"))
      (node (ref "JB88") (pin "1") (pinfunction "1_1") (pintype "passive"))
    )
    (net (code "118") (name "Net-(J22-P$1)") (class "Default")
      (node (ref "J22") (pin "1") (pinfunction "P$1_1") (pintype "bidirectional"))
      (node (ref "J27") (pin "2") (pinfunction "P$2_2") (pintype "bidirectional"))
    )
    (net (code "119") (name "Net-(J22-P$2)") (class "Default")
      (node (ref "J22") (pin "2") (pinfunction "P$2_2") (pintype "bidirectional"))
      (node (ref "J35") (pin "1") (pinfunction "P$1_1") (pintype "bidirectional"))
    )
    (net (code "120") (name "Net-(J23-P$1)") (class "Default")
      (node (ref "J23") (pin "1") (pinfunction "P$1_1") (pintype "bidirectional"))
      (node (ref "J46") (pin "2") (pinfunction "P$2_2") (pintype "bidirectional"))
    )
    (net (code "121") (name "Net-(J24-P$1)") (class "Default")
      (node (ref "J24") (pin "1") (pinfunction "P$1_1") (pintype "bidirectional"))
      (node (ref "J25") (pin "2") (pinfunction "P$2_2") (pintype "bidirectional"))
    )
    (net (code "122") (name "Net-(J26-P$1)") (class "Default")
      (node (ref "J26") (pin "1") (pinfunction "P$1_1") (pintype "bidirectional"))
      (node (ref "J33") (pin "2") (pinfunction "P$2_2") (pintype "bidirectional"))
    )
    (net (code "123") (name "Net-(J28-P$2)") (class "Default")
      (node (ref "J28") (pin "2") (pinfunction "P$2_2") (pintype "bidirectional"))
      (node (ref "J30") (pin "1") (pinfunction "P$1_1") (pintype "bidirectional"))
    )
    (net (code "124") (name "Net-(J29-P$2)") (class "Default")
      (node (ref "J29") (pin "2") (pinfunction "P$2_2") (pintype "bidirectional"))
      (node (ref "J31") (pin "1") (pinfunction "P$1_1") (pintype "bidirectional"))
    )
    (net (code "125") (name "Net-(J30-P$2)") (class "Default")
      (node (ref "J30") (pin "2") (pinfunction "P$2_2") (pintype "bidirectional"))
      (node (ref "J36") (pin "1") (pinfunction "P$1_1") (pintype "bidirectional"))
    )
    (net (code "126") (name "Net-(J31-P$2)") (class "Default")
      (node (ref "J31") (pin "2") (pinfunction "P$2_2") (pintype "bidirectional"))
      (node (ref "J37") (pin "1") (pinfunction "P$1_1") (pintype "bidirectional"))
    )
    (net (code "127") (name "Net-(J32-P$2)") (class "Default")
      (node (ref "J32") (pin "2") (pinfunction "P$2_2") (pintype "bidirectional"))
      (node (ref "J41") (pin "1") (pinfunction "P$1_1") (pintype "bidirectional"))
    )
    (net (code "128") (name "Net-(J34-P$2)") (class "Default")
      (node (ref "J34") (pin "2") (pinfunction "P$2_2") (pintype "bidirectional"))
      (node (ref "J43") (pin "1") (pinfunction "P$1_1") (pintype "bidirectional"))
    )
    (net (code "129") (name "Net-(J35-P$2)") (class "Default")
      (node (ref "J35") (pin "2") (pinfunction "P$2_2") (pintype "bidirectional"))
      (node (ref "J38") (pin "1") (pinfunction "P$1_1") (pintype "bidirectional"))
    )
    (net (code "130") (name "Net-(J36-P$2)") (class "Default")
      (node (ref "J36") (pin "2") (pinfunction "P$2_2") (pintype "bidirectional"))
      (node (ref "J39") (pin "1") (pinfunction "P$1_1") (pintype "bidirectional"))
    )
    (net (code "131") (name "Net-(J37-P$2)") (class "Default")
      (node (ref "J37") (pin "2") (pinfunction "P$2_2") (pintype "bidirectional"))
      (node (ref "J40") (pin "1") (pinfunction "P$1_1") (pintype "bidirectional"))
    )
    (net (code "132") (name "Net-(J48-P$1)") (class "Default")
      (node (ref "J48") (pin "1") (pinfunction "P$1_1") (pintype "bidirectional"))
      (node (ref "J49") (pin "2") (pinfunction "P$2_2") (pintype "bidirectional"))
    )
    (net (code "133") (name "Net-(J50-P$1)") (class "Default")
      (node (ref "J50") (pin "1") (pinfunction "P$1_1") (pintype "bidirectional"))
      (node (ref "J51") (pin "2") (pinfunction "P$2_2") (pintype "bidirectional"))
    )
    (net (code "134") (name "Net-(J52-P$1)") (class "Default")
      (node (ref "J52") (pin "1") (pinfunction "P$1_1") (pintype "bidirectional"))
      (node (ref "J53") (pin "2") (pinfunction "P$2_2") (pintype "bidirectional"))
    )
    (net (code "135") (name "Net-(J54-P$1)") (class "Default")
      (node (ref "J54") (pin "1") (pinfunction "P$1_1") (pintype "bidirectional"))
      (node (ref "J55") (pin "2") (pinfunction "P$2_2") (pintype "bidirectional"))
    )
    (net (code "136") (name "Net-(J56-P$1)") (class "Default")
      (node (ref "J56") (pin "1") (pinfunction "P$1_1") (pintype "bidirectional"))
      (node (ref "J57") (pin "2") (pinfunction "P$2_2") (pintype "bidirectional"))
    )
    (net (code "137") (name "Net-(R3-Pad2)") (class "Default")
      (node (ref "R3") (pin "2") (pinfunction "2_2") (pintype "passive"))
      (node (ref "R6") (pin "1") (pinfunction "1_1") (pintype "passive"))
    )
    (net (code "138") (name "Net-(S1A-PIN-1)") (class "Default")
      (node (ref "JB1") (pin "2") (pinfunction "2_2") (pintype "passive"))
      (node (ref "S1") (pin "SW1") (pinfunction "PIN-1_SW1") (pintype "passive"))
    )
    (net (code "139") (name "Net-(S1A-PIN-2)") (class "Default")
      (node (ref "JA1") (pin "1") (pinfunction "1_1") (pintype "passive"))
      (node (ref "S1") (pin "SW2") (pinfunction "PIN-2_SW2") (pintype "passive"))
    )
    (net (code "140") (name "Net-(S2A-PIN-1)") (class "Default")
      (node (ref "JB2") (pin "2") (pinfunction "2_2") (pintype "passive"))
      (node (ref "S2") (pin "SW1") (pinfunction "PIN-1_SW1") (pintype "passive"))
    )
    (net (code "141") (name "Net-(S2A-PIN-2)") (class "Default")
      (node (ref "JA2") (pin "1") (pinfunction "1_1") (pintype "passive"))
      (node (ref "S2") (pin "SW2") (pinfunction "PIN-2_SW2") (pintype "passive"))
    )
    (net (code "142") (name "Net-(S3A-PIN-1)") (class "Default")
      (node (ref "JA3") (pin "1") (pinfunction "1_1") (pintype "passive"))
      (node (ref "S3") (pin "SW1") (pinfunction "PIN-1_SW1") (pintype "passive"))
    )
    (net (code "143") (name "Net-(S3A-PIN-2)") (class "Default")
      (node (ref "JB3") (pin "2") (pinfunction "2_2") (pintype "passive"))
      (node (ref "S3") (pin "SW2") (pinfunction "PIN-2_SW2") (pintype "passive"))
    )
    (net (code "144") (name "Net-(S4A-PIN-1)") (class "Default")
      (node (ref "JA4") (pin "1") (pinfunction "1_1") (pintype "passive"))
      (node (ref "S4") (pin "SW1") (pinfunction "PIN-1_SW1") (pintype "passive"))
    )
    (net (code "145") (name "Net-(S4A-PIN-2)") (class "Default")
      (node (ref "JB4") (pin "2") (pinfunction "2_2") (pintype "passive"))
      (node (ref "S4") (pin "SW2") (pinfunction "PIN-2_SW2") (pintype "passive"))
    )
    (net (code "146") (name "Net-(S5A-PIN-1)") (class "Default")
      (node (ref "JB5") (pin "2") (pinfunction "2_2") (pintype "passive"))
      (node (ref "S5") (pin "SW1") (pinfunction "PIN-1_SW1") (pintype "passive"))
    )
    (net (code "147") (name "Net-(S5A-PIN-2)") (class "Default")
      (node (ref "JA5") (pin "1") (pinfunction "1_1") (pintype "passive"))
      (node (ref "S5") (pin "SW2") (pinfunction "PIN-2_SW2") (pintype "passive"))
    )
    (net (code "148") (name "Net-(S6A-PIN-1)") (class "Default")
      (node (ref "JB6") (pin "2") (pinfunction "2_2") (pintype "passive"))
      (node (ref "S6") (pin "SW1") (pinfunction "PIN-1_SW1") (pintype "passive"))
    )
    (net (code "149") (name "Net-(S6A-PIN-2)") (class "Default")
      (node (ref "JA6") (pin "1") (pinfunction "1_1") (pintype "passive"))
      (node (ref "S6") (pin "SW2") (pinfunction "PIN-2_SW2") (pintype "passive"))
    )
    (net (code "150") (name "Net-(S7A-PIN-1)") (class "Default")
      (node (ref "JB7") (pin "2") (pinfunction "2_2") (pintype "passive"))
      (node (ref "S7") (pin "SW1") (pinfunction "PIN-1_SW1") (pintype "passive"))
    )
    (net (code "151") (name "Net-(S7A-PIN-2)") (class "Default")
      (node (ref "JA7") (pin "1") (pinfunction "1_1") (pintype "passive"))
      (node (ref "S7") (pin "SW2") (pinfunction "PIN-2_SW2") (pintype "passive"))
    )
    (net (code "152") (name "Net-(S8A-PIN-1)") (class "Default")
      (node (ref "JB8") (pin "2") (pinfunction "2_2") (pintype "passive"))
      (node (ref "S8") (pin "SW1") (pinfunction "PIN-1_SW1") (pintype "passive"))
    )
    (net (code "153") (name "Net-(S8A-PIN-2)") (class "Default")
      (node (ref "JA8") (pin "1") (pinfunction "1_1") (pintype "passive"))
      (node (ref "S8") (pin "SW2") (pinfunction "PIN-2_SW2") (pintype "passive"))
    )
    (net (code "154") (name "Net-(S9A-PIN-1)") (class "Default")
      (node (ref "JB9") (pin "2") (pinfunction "2_2") (pintype "passive"))
      (node (ref "S9") (pin "SW1") (pinfunction "PIN-1_SW1") (pintype "passive"))
    )
    (net (code "155") (name "Net-(S9A-PIN-2)") (class "Default")
      (node (ref "JA9") (pin "1") (pinfunction "1_1") (pintype "passive"))
      (node (ref "S9") (pin "SW2") (pinfunction "PIN-2_SW2") (pintype "passive"))
    )
    (net (code "156") (name "Net-(S10A-PIN-1)") (class "Default")
      (node (ref "JA10") (pin "1") (pinfunction "1_1") (pintype "passive"))
      (node (ref "S10") (pin "SW1") (pinfunction "PIN-1_SW1") (pintype "passive"))
    )
    (net (code "157") (name "Net-(S10A-PIN-2)") (class "Default")
      (node (ref "JB10") (pin "2") (pinfunction "2_2") (pintype "passive"))
      (node (ref "S10") (pin "SW2") (pinfunction "PIN-2_SW2") (pintype "passive"))
    )
    (net (code "158") (name "Net-(S11A-PIN-1)") (class "Default")
      (node (ref "JB11") (pin "2") (pinfunction "2_2") (pintype "passive"))
      (node (ref "S11") (pin "SW1") (pinfunction "PIN-1_SW1") (pintype "passive"))
    )
    (net (code "159") (name "Net-(S11A-PIN-2)") (class "Default")
      (node (ref "JA11") (pin "1") (pinfunction "1_1") (pintype "passive"))
      (node (ref "S11") (pin "SW2") (pinfunction "PIN-2_SW2") (pintype "passive"))
    )
    (net (code "160") (name "Net-(S12A-PIN-1)") (class "Default")
      (node (ref "JB12") (pin "2") (pinfunction "2_2") (pintype "passive"))
      (node (ref "S12") (pin "SW1") (pinfunction "PIN-1_SW1") (pintype "passive"))
    )
    (net (code "161") (name "Net-(S12A-PIN-2)") (class "Default")
      (node (ref "JA12") (pin "1") (pinfunction "1_1") (pintype "passive"))
      (node (ref "S12") (pin "SW2") (pinfunction "PIN-2_SW2") (pintype "passive"))
    )
    (net (code "162") (name "Net-(S13A-PIN-1)") (class "Default")
      (node (ref "JB13") (pin "2") (pinfunction "2_2") (pintype "passive"))
      (node (ref "S13") (pin "SW1") (pinfunction "PIN-1_SW1") (pintype "passive"))
    )
    (net (code "163") (name "Net-(S13A-PIN-2)") (class "Default")
      (node (ref "JA13") (pin "1") (pinfunction "1_1") (pintype "passive"))
      (node (ref "S13") (pin "SW2") (pinfunction "PIN-2_SW2") (pintype "passive"))
    )
    (net (code "164") (name "Net-(S14A-PIN-1)") (class "Default")
      (node (ref "JB14") (pin "2") (pinfunction "2_2") (pintype "passive"))
      (node (ref "S14") (pin "SW1") (pinfunction "PIN-1_SW1") (pintype "passive"))
    )
    (net (code "165") (name "Net-(S14A-PIN-2)") (class "Default")
      (node (ref "JA14") (pin "1") (pinfunction "1_1") (pintype "passive"))
      (node (ref "S14") (pin "SW2") (pinfunction "PIN-2_SW2") (pintype "passive"))
    )
    (net (code "166") (name "Net-(S15A-PIN-1)") (class "Default")
      (node (ref "JB15") (pin "2") (pinfunction "2_2") (pintype "passive"))
      (node (ref "S15") (pin "SW1") (pinfunction "PIN-1_SW1") (pintype "passive"))
    )
    (net (code "167") (name "Net-(S15A-PIN-2)") (class "Default")
      (node (ref "JA15") (pin "1") (pinfunction "1_1") (pintype "passive"))
      (node (ref "S15") (pin "SW2") (pinfunction "PIN-2_SW2") (pintype "passive"))
    )
    (net (code "168") (name "Net-(S16A-PIN-1)") (class "Default")
      (node (ref "JB16") (pin "2") (pinfunction "2_2") (pintype "passive"))
      (node (ref "S16") (pin "SW1") (pinfunction "PIN-1_SW1") (pintype "passive"))
    )
    (net (code "169") (name "Net-(S16A-PIN-2)") (class "Default")
      (node (ref "JA16") (pin "1") (pinfunction "1_1") (pintype "passive"))
      (node (ref "S16") (pin "SW2") (pinfunction "PIN-2_SW2") (pintype "passive"))
    )
    (net (code "170") (name "Net-(S17A-PIN-1)") (class "Default")
      (node (ref "JB17") (pin "2") (pinfunction "2_2") (pintype "passive"))
      (node (ref "S17") (pin "SW1") (pinfunction "PIN-1_SW1") (pintype "passive"))
    )
    (net (code "171") (name "Net-(S17A-PIN-2)") (class "Default")
      (node (ref "JA17") (pin "1") (pinfunction "1_1") (pintype "passive"))
      (node (ref "S17") (pin "SW2") (pinfunction "PIN-2_SW2") (pintype "passive"))
    )
    (net (code "172") (name "Net-(S18A-PIN-1)") (class "Default")
      (node (ref "JB18") (pin "2") (pinfunction "2_2") (pintype "passive"))
      (node (ref "S18") (pin "SW1") (pinfunction "PIN-1_SW1") (pintype "passive"))
    )
    (net (code "173") (name "Net-(S18A-PIN-2)") (class "Default")
      (node (ref "JA18") (pin "1") (pinfunction "1_1") (pintype "passive"))
      (node (ref "S18") (pin "SW2") (pinfunction "PIN-2_SW2") (pintype "passive"))
    )
    (net (code "174") (name "Net-(S19A-PIN-1)") (class "Default")
      (node (ref "JB19") (pin "2") (pinfunction "2_2") (pintype "passive"))
      (node (ref "S19") (pin "SW1") (pinfunction "PIN-1_SW1") (pintype "passive"))
    )
    (net (code "175") (name "Net-(S19A-PIN-2)") (class "Default")
      (node (ref "JA19") (pin "1") (pinfunction "1_1") (pintype "passive"))
      (node (ref "S19") (pin "SW2") (pinfunction "PIN-2_SW2") (pintype "passive"))
    )
    (net (code "176") (name "Net-(S20A-PIN-1)") (class "Default")
      (node (ref "JB20") (pin "2") (pinfunction "2_2") (pintype "passive"))
      (node (ref "S20") (pin "SW1") (pinfunction "PIN-1_SW1") (pintype "passive"))
    )
    (net (code "177") (name "Net-(S20A-PIN-2)") (class "Default")
      (node (ref "JA20") (pin "1") (pinfunction "1_1") (pintype "passive"))
      (node (ref "S20") (pin "SW2") (pinfunction "PIN-2_SW2") (pintype "passive"))
    )
    (net (code "178") (name "Net-(S21A-PIN-1)") (class "Default")
      (node (ref "JB21") (pin "2") (pinfunction "2_2") (pintype "passive"))
      (node (ref "S21") (pin "SW1") (pinfunction "PIN-1_SW1") (pintype "passive"))
    )
    (net (code "179") (name "Net-(S21A-PIN-2)") (class "Default")
      (node (ref "JA21") (pin "1") (pinfunction "1_1") (pintype "passive"))
      (node (ref "S21") (pin "SW2") (pinfunction "PIN-2_SW2") (pintype "passive"))
    )
    (net (code "180") (name "Net-(S22A-PIN-1)") (class "Default")
      (node (ref "JB22") (pin "2") (pinfunction "2_2") (pintype "passive"))
      (node (ref "S22") (pin "SW1") (pinfunction "PIN-1_SW1") (pintype "passive"))
    )
    (net (code "181") (name "Net-(S22A-PIN-2)") (class "Default")
      (node (ref "JA22") (pin "1") (pinfunction "1_1") (pintype "passive"))
      (node (ref "S22") (pin "SW2") (pinfunction "PIN-2_SW2") (pintype "passive"))
    )
    (net (code "182") (name "Net-(S23A-PIN-1)") (class "Default")
      (node (ref "JB23") (pin "2") (pinfunction "2_2") (pintype "passive"))
      (node (ref "S23") (pin "SW1") (pinfunction "PIN-1_SW1") (pintype "passive"))
    )
    (net (code "183") (name "Net-(S23A-PIN-2)") (class "Default")
      (node (ref "JA23") (pin "1") (pinfunction "1_1") (pintype "passive"))
      (node (ref "S23") (pin "SW2") (pinfunction "PIN-2_SW2") (pintype "passive"))
    )
    (net (code "184") (name "Net-(S24A-PIN-1)") (class "Default")
      (node (ref "JA24") (pin "1") (pinfunction "1_1") (pintype "passive"))
      (node (ref "S24") (pin "SW1") (pinfunction "PIN-1_SW1") (pintype "passive"))
    )
    (net (code "185") (name "Net-(S24A-PIN-2)") (class "Default")
      (node (ref "JB24") (pin "2") (pinfunction "2_2") (pintype "passive"))
      (node (ref "S24") (pin "SW2") (pinfunction "PIN-2_SW2") (pintype "passive"))
    )
    (net (code "186") (name "Net-(S25A-PIN-1)") (class "Default")
      (node (ref "JB25") (pin "2") (pinfunction "2_2") (pintype "passive"))
      (node (ref "S25") (pin "SW1") (pinfunction "PIN-1_SW1") (pintype "passive"))
    )
    (net (code "187") (name "Net-(S25A-PIN-2)") (class "Default")
      (node (ref "JA25") (pin "1") (pinfunction "1_1") (pintype "passive"))
      (node (ref "S25") (pin "SW2") (pinfunction "PIN-2_SW2") (pintype "passive"))
    )
    (net (code "188") (name "Net-(S26A-PIN-1)") (class "Default")
      (node (ref "JB26") (pin "2") (pinfunction "2_2") (pintype "passive"))
      (node (ref "S26") (pin "SW1") (pinfunction "PIN-1_SW1") (pintype "passive"))
    )
    (net (code "189") (name "Net-(S26A-PIN-2)") (class "Default")
      (node (ref "JA26") (pin "1") (pinfunction "1_1") (pintype "passive"))
      (node (ref "S26") (pin "SW2") (pinfunction "PIN-2_SW2") (pintype "passive"))
    )
    (net (code "190") (name "Net-(S27A-PIN-1)") (class "Default")
      (node (ref "JB27") (pin "2") (pinfunction "2_2") (pintype "passive"))
      (node (ref "S27") (pin "SW1") (pinfunction "PIN-1_SW1") (pintype "passive"))
    )
    (net (code "191") (name "Net-(S27A-PIN-2)") (class "Default")
      (node (ref "JA27") (pin "1") (pinfunction "1_1") (pintype "passive"))
      (node (ref "S27") (pin "SW2") (pinfunction "PIN-2_SW2") (pintype "passive"))
    )
    (net (code "192") (name "Net-(S28A-PIN-1)") (class "Default")
      (node (ref "JB28") (pin "2") (pinfunction "2_2") (pintype "passive"))
      (node (ref "S28") (pin "SW1") (pinfunction "PIN-1_SW1") (pintype "passive"))
    )
    (net (code "193") (name "Net-(S28A-PIN-2)") (class "Default")
      (node (ref "JA28") (pin "1") (pinfunction "1_1") (pintype "passive"))
      (node (ref "S28") (pin "SW2") (pinfunction "PIN-2_SW2") (pintype "passive"))
    )
    (net (code "194") (name "Net-(S29A-PIN-1)") (class "Default")
      (node (ref "JB29") (pin "2") (pinfunction "2_2") (pintype "passive"))
      (node (ref "S29") (pin "SW1") (pinfunction "PIN-1_SW1") (pintype "passive"))
    )
    (net (code "195") (name "Net-(S29A-PIN-2)") (class "Default")
      (node (ref "JA29") (pin "1") (pinfunction "1_1") (pintype "passive"))
      (node (ref "S29") (pin "SW2") (pinfunction "PIN-2_SW2") (pintype "passive"))
    )
    (net (code "196") (name "Net-(S30A-PIN-1)") (class "Default")
      (node (ref "JB30") (pin "2") (pinfunction "2_2") (pintype "passive"))
      (node (ref "S30") (pin "SW1") (pinfunction "PIN-1_SW1") (pintype "passive"))
    )
    (net (code "197") (name "Net-(S30A-PIN-2)") (class "Default")
      (node (ref "JA30") (pin "1") (pinfunction "1_1") (pintype "passive"))
      (node (ref "S30") (pin "SW2") (pinfunction "PIN-2_SW2") (pintype "passive"))
    )
    (net (code "198") (name "Net-(S31A-PIN-1)") (class "Default")
      (node (ref "JB31") (pin "2") (pinfunction "2_2") (pintype "passive"))
      (node (ref "S31") (pin "SW1") (pinfunction "PIN-1_SW1") (pintype "passive"))
    )
    (net (code "199") (name "Net-(S31A-PIN-2)") (class "Default")
      (node (ref "JA31") (pin "1") (pinfunction "1_1") (pintype "passive"))
      (node (ref "S31") (pin "SW2") (pinfunction "PIN-2_SW2") (pintype "passive"))
    )
    (net (code "200") (name "Net-(S32A-PIN-1)") (class "Default")
      (node (ref "JB32") (pin "2") (pinfunction "2_2") (pintype "passive"))
      (node (ref "S32") (pin "SW1") (pinfunction "PIN-1_SW1") (pintype "passive"))
    )
    (net (code "201") (name "Net-(S32A-PIN-2)") (class "Default")
      (node (ref "JA32") (pin "1") (pinfunction "1_1") (pintype "passive"))
      (node (ref "S32") (pin "SW2") (pinfunction "PIN-2_SW2") (pintype "passive"))
    )
    (net (code "202") (name "Net-(S33A-PIN-1)") (class "Default")
      (node (ref "JB33") (pin "2") (pinfunction "2_2") (pintype "passive"))
      (node (ref "S33") (pin "SW1") (pinfunction "PIN-1_SW1") (pintype "passive"))
    )
    (net (code "203") (name "Net-(S33A-PIN-2)") (class "Default")
      (node (ref "JA33") (pin "1") (pinfunction "1_1") (pintype "passive"))
      (node (ref "S33") (pin "SW2") (pinfunction "PIN-2_SW2") (pintype "passive"))
    )
    (net (code "204") (name "Net-(S34A-PIN-1)") (class "Default")
      (node (ref "JB34") (pin "2") (pinfunction "2_2") (pintype "passive"))
      (node (ref "S34") (pin "SW1") (pinfunction "PIN-1_SW1") (pintype "passive"))
    )
    (net (code "205") (name "Net-(S34A-PIN-2)") (class "Default")
      (node (ref "JA34") (pin "1") (pinfunction "1_1") (pintype "passive"))
      (node (ref "S34") (pin "SW2") (pinfunction "PIN-2_SW2") (pintype "passive"))
    )
    (net (code "206") (name "Net-(S35A-PIN-1)") (class "Default")
      (node (ref "JB35") (pin "2") (pinfunction "2_2") (pintype "passive"))
      (node (ref "S35") (pin "SW1") (pinfunction "PIN-1_SW1") (pintype "passive"))
    )
    (net (code "207") (name "Net-(S35A-PIN-2)") (class "Default")
      (node (ref "JA35") (pin "1") (pinfunction "1_1") (pintype "passive"))
      (node (ref "S35") (pin "SW2") (pinfunction "PIN-2_SW2") (pintype "passive"))
    )
    (net (code "208") (name "Net-(S36A-PIN-1)") (class "Default")
      (node (ref "JB36") (pin "2") (pinfunction "2_2") (pintype "passive"))
      (node (ref "S36") (pin "SW1") (pinfunction "PIN-1_SW1") (pintype "passive"))
    )
    (net (code "209") (name "Net-(S36A-PIN-2)") (class "Default")
      (node (ref "JA36") (pin "1") (pinfunction "1_1") (pintype "passive"))
      (node (ref "S36") (pin "SW2") (pinfunction "PIN-2_SW2") (pintype "passive"))
    )
    (net (code "210") (name "Net-(S37A-PIN-1)") (class "Default")
      (node (ref "JA37") (pin "1") (pinfunction "1_1") (pintype "passive"))
      (node (ref "S37") (pin "SW1") (pinfunction "PIN-1_SW1") (pintype "passive"))
    )
    (net (code "211") (name "Net-(S37A-PIN-2)") (class "Default")
      (node (ref "JB37") (pin "2") (pinfunction "2_2") (pintype "passive"))
      (node (ref "S37") (pin "SW2") (pinfunction "PIN-2_SW2") (pintype "passive"))
    )
    (net (code "212") (name "Net-(S38A-PIN-1)") (class "Default")
      (node (ref "JA38") (pin "1") (pinfunction "1_1") (pintype "passive"))
      (node (ref "S38") (pin "SW1") (pinfunction "PIN-1_SW1") (pintype "passive"))
    )
    (net (code "213") (name "Net-(S38A-PIN-2)") (class "Default")
      (node (ref "JB38") (pin "2") (pinfunction "2_2") (pintype "passive"))
      (node (ref "S38") (pin "SW2") (pinfunction "PIN-2_SW2") (pintype "passive"))
    )
    (net (code "214") (name "Net-(S39A-PIN-1)") (class "Default")
      (node (ref "JA39") (pin "1") (pinfunction "1_1") (pintype "passive"))
      (node (ref "S39") (pin "SW1") (pinfunction "PIN-1_SW1") (pintype "passive"))
    )
    (net (code "215") (name "Net-(S39A-PIN-2)") (class "Default")
      (node (ref "JB39") (pin "2") (pinfunction "2_2") (pintype "passive"))
      (node (ref "S39") (pin "SW2") (pinfunction "PIN-2_SW2") (pintype "passive"))
    )
    (net (code "216") (name "Net-(S40A-PIN-1)") (class "Default")
      (node (ref "JA40") (pin "1") (pinfunction "1_1") (pintype "passive"))
      (node (ref "S40") (pin "SW1") (pinfunction "PIN-1_SW1") (pintype "passive"))
    )
    (net (code "217") (name "Net-(S40A-PIN-2)") (class "Default")
      (node (ref "JB40") (pin "2") (pinfunction "2_2") (pintype "passive"))
      (node (ref "S40") (pin "SW2") (pinfunction "PIN-2_SW2") (pintype "passive"))
    )
    (net (code "218") (name "Net-(S41A-PIN-1)") (class "Default")
      (node (ref "JA41") (pin "1") (pinfunction "1_1") (pintype "passive"))
      (node (ref "S41") (pin "SW1") (pinfunction "PIN-1_SW1") (pintype "passive"))
    )
    (net (code "219") (name "Net-(S41A-PIN-2)") (class "Default")
      (node (ref "JB41") (pin "2") (pinfunction "2_2") (pintype "passive"))
      (node (ref "S41") (pin "SW2") (pinfunction "PIN-2_SW2") (pintype "passive"))
    )
    (net (code "220") (name "Net-(S42A-PIN-1)") (class "Default")
      (node (ref "JA42") (pin "1") (pinfunction "1_1") (pintype "passive"))
      (node (ref "S42") (pin "SW1") (pinfunction "PIN-1_SW1") (pintype "passive"))
    )
    (net (code "221") (name "Net-(S42A-PIN-2)") (class "Default")
      (node (ref "JB42") (pin "2") (pinfunction "2_2") (pintype "passive"))
      (node (ref "S42") (pin "SW2") (pinfunction "PIN-2_SW2") (pintype "passive"))
    )
    (net (code "222") (name "Net-(S45A-PIN-1)") (class "Default")
      (node (ref "JB45") (pin "2") (pinfunction "2_2") (pintype "passive"))
      (node (ref "S45") (pin "SW1") (pinfunction "PIN-1_SW1") (pintype "passive"))
    )
    (net (code "223") (name "Net-(S45A-PIN-2)") (class "Default")
      (node (ref "JA45") (pin "1") (pinfunction "1_1") (pintype "passive"))
      (node (ref "S45") (pin "SW2") (pinfunction "PIN-2_SW2") (pintype "passive"))
    )
    (net (code "224") (name "Net-(S46A-PIN-1)") (class "Default")
      (node (ref "JB46") (pin "2") (pinfunction "2_2") (pintype "passive"))
      (node (ref "S46") (pin "SW1") (pinfunction "PIN-1_SW1") (pintype "passive"))
    )
    (net (code "225") (name "Net-(S46A-PIN-2)") (class "Default")
      (node (ref "JA46") (pin "1") (pinfunction "1_1") (pintype "passive"))
      (node (ref "S46") (pin "SW2") (pinfunction "PIN-2_SW2") (pintype "passive"))
    )
    (net (code "226") (name "Net-(S88A-PIN-1)") (class "Default")
      (node (ref "JB88") (pin "2") (pinfunction "2_2") (pintype "passive"))
      (node (ref "S88") (pin "SW1") (pinfunction "PIN-1_SW1") (pintype "passive"))
    )
    (net (code "227") (name "Net-(S88A-PIN-2)") (class "Default")
      (node (ref "JA88") (pin "1") (pinfunction "1_1") (pintype "passive"))
      (node (ref "S88") (pin "SW2") (pinfunction "PIN-2_SW2") (pintype "passive"))
    )
  )
)
